# TRV-Controller.net
KiCad netlist of a schematic drawn in EasyEDA Pro
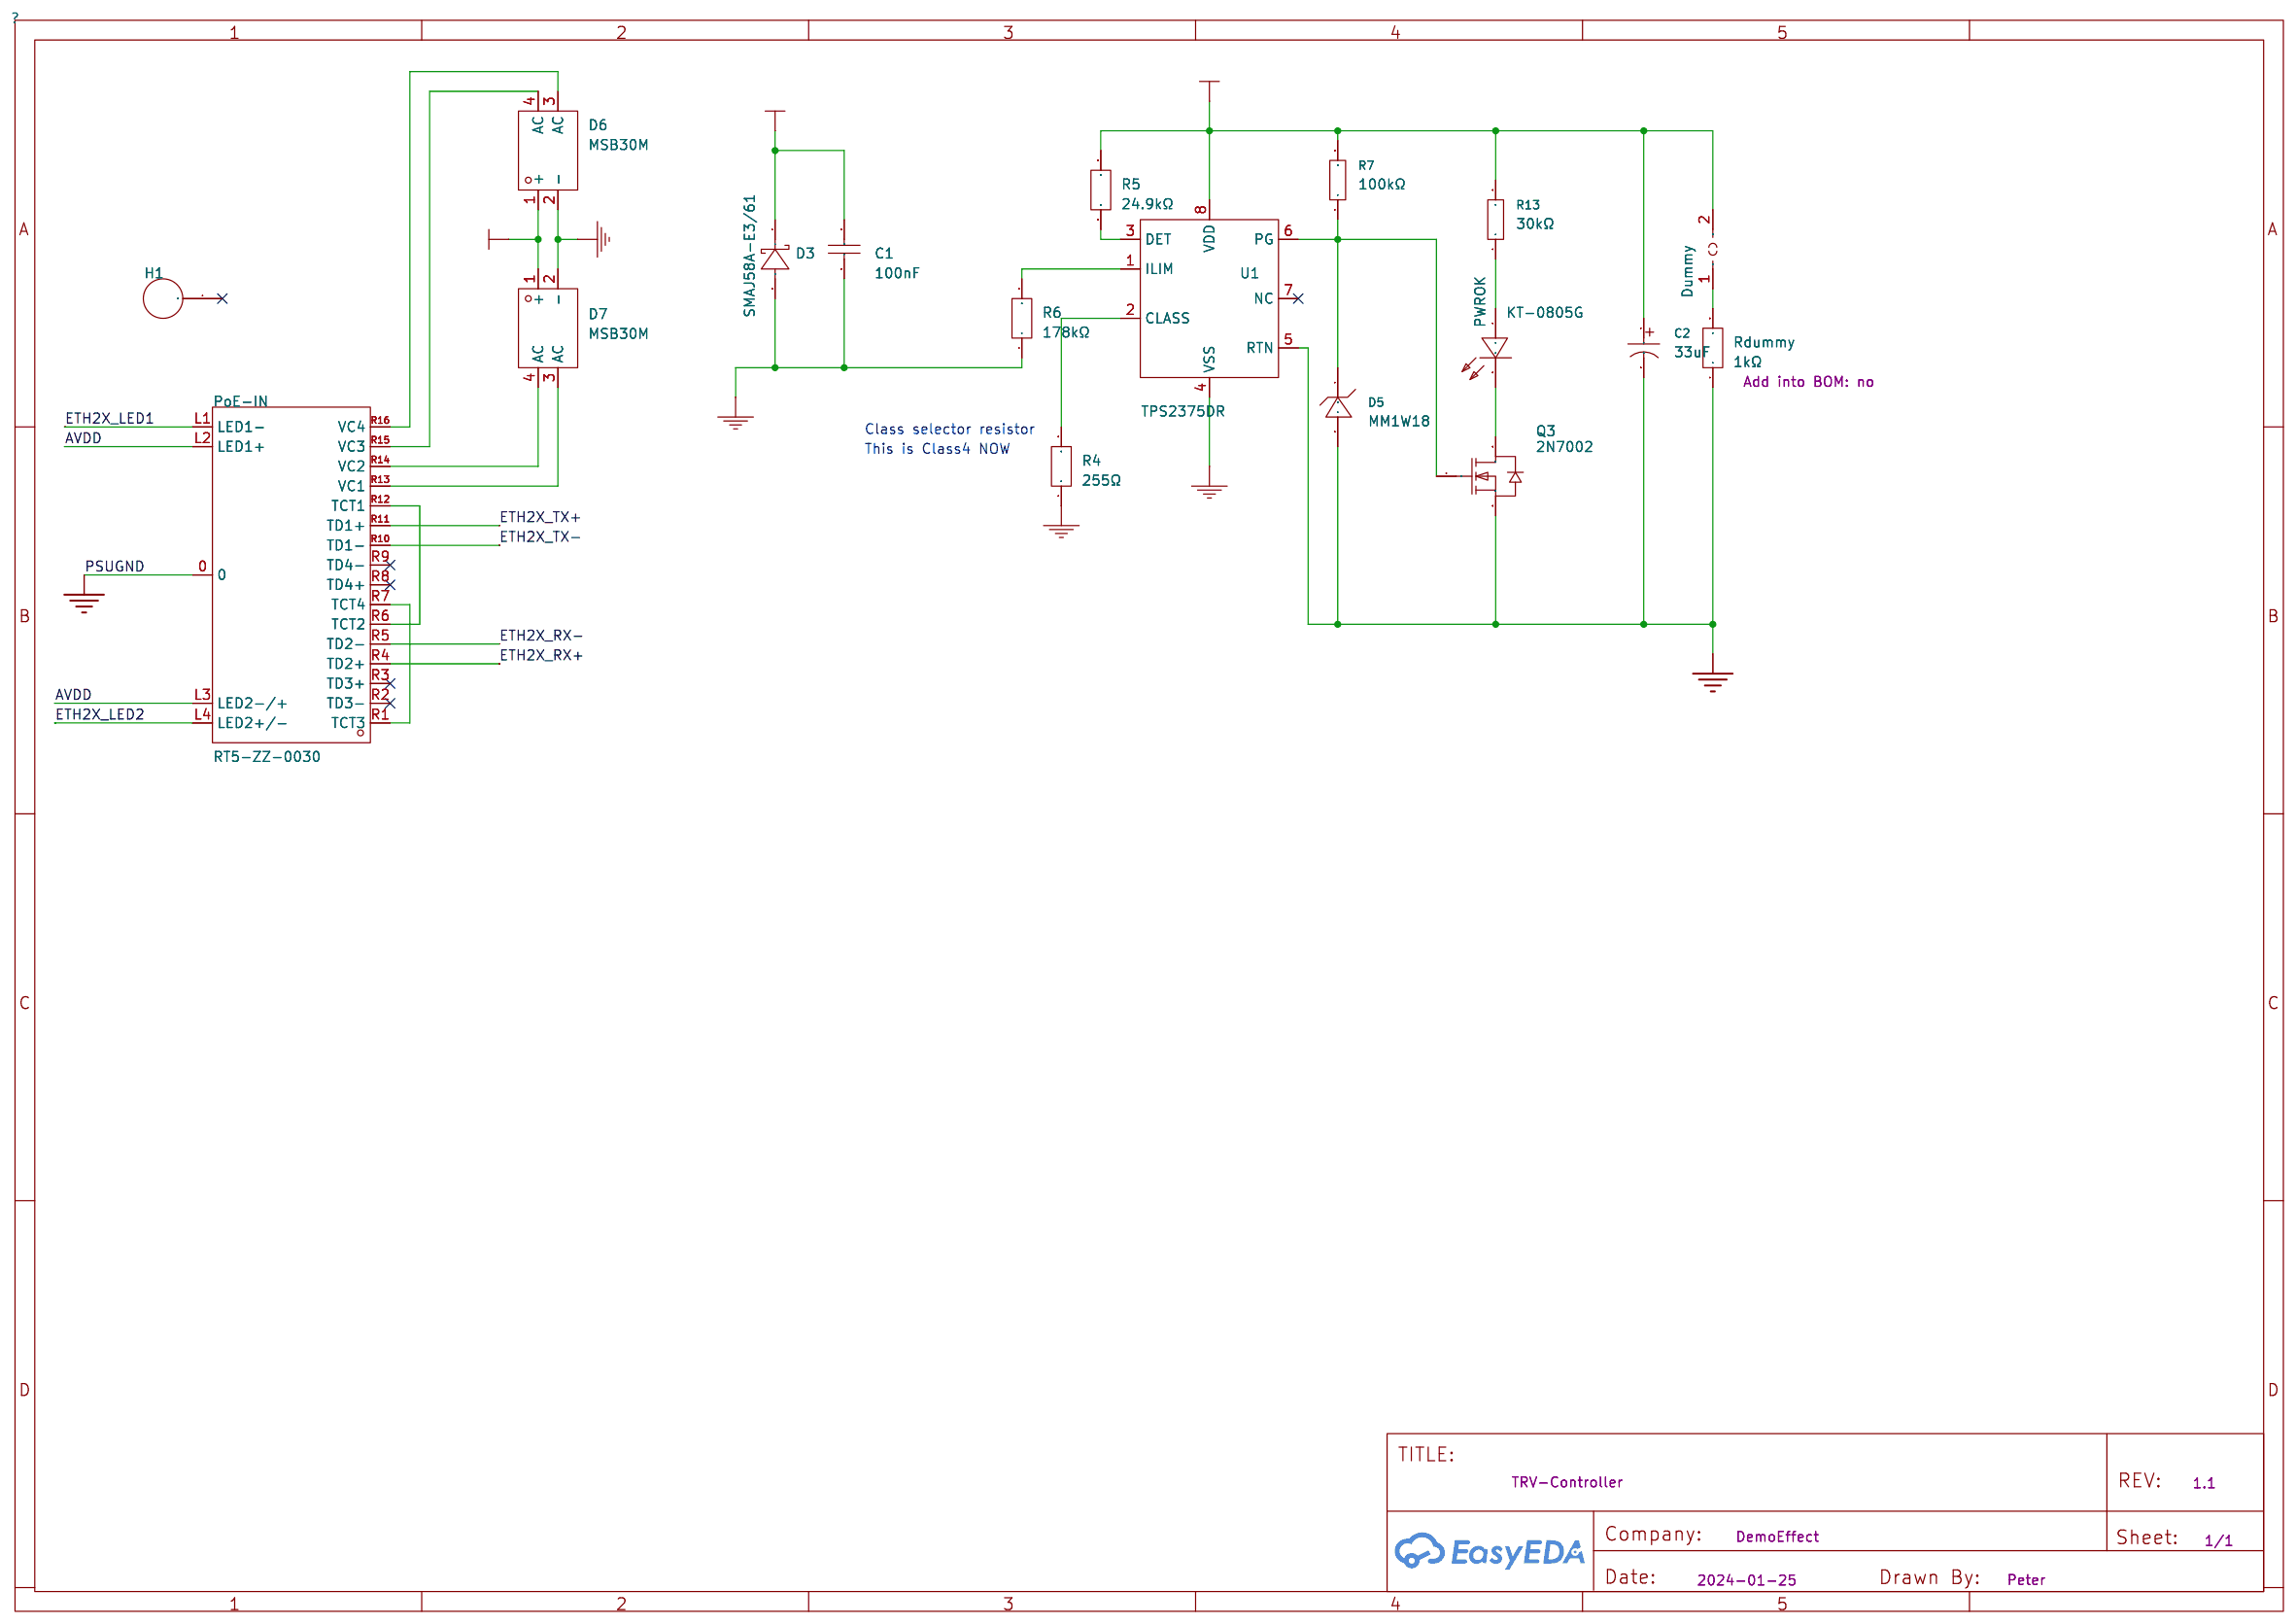
[diagram p0: PoE isolator]
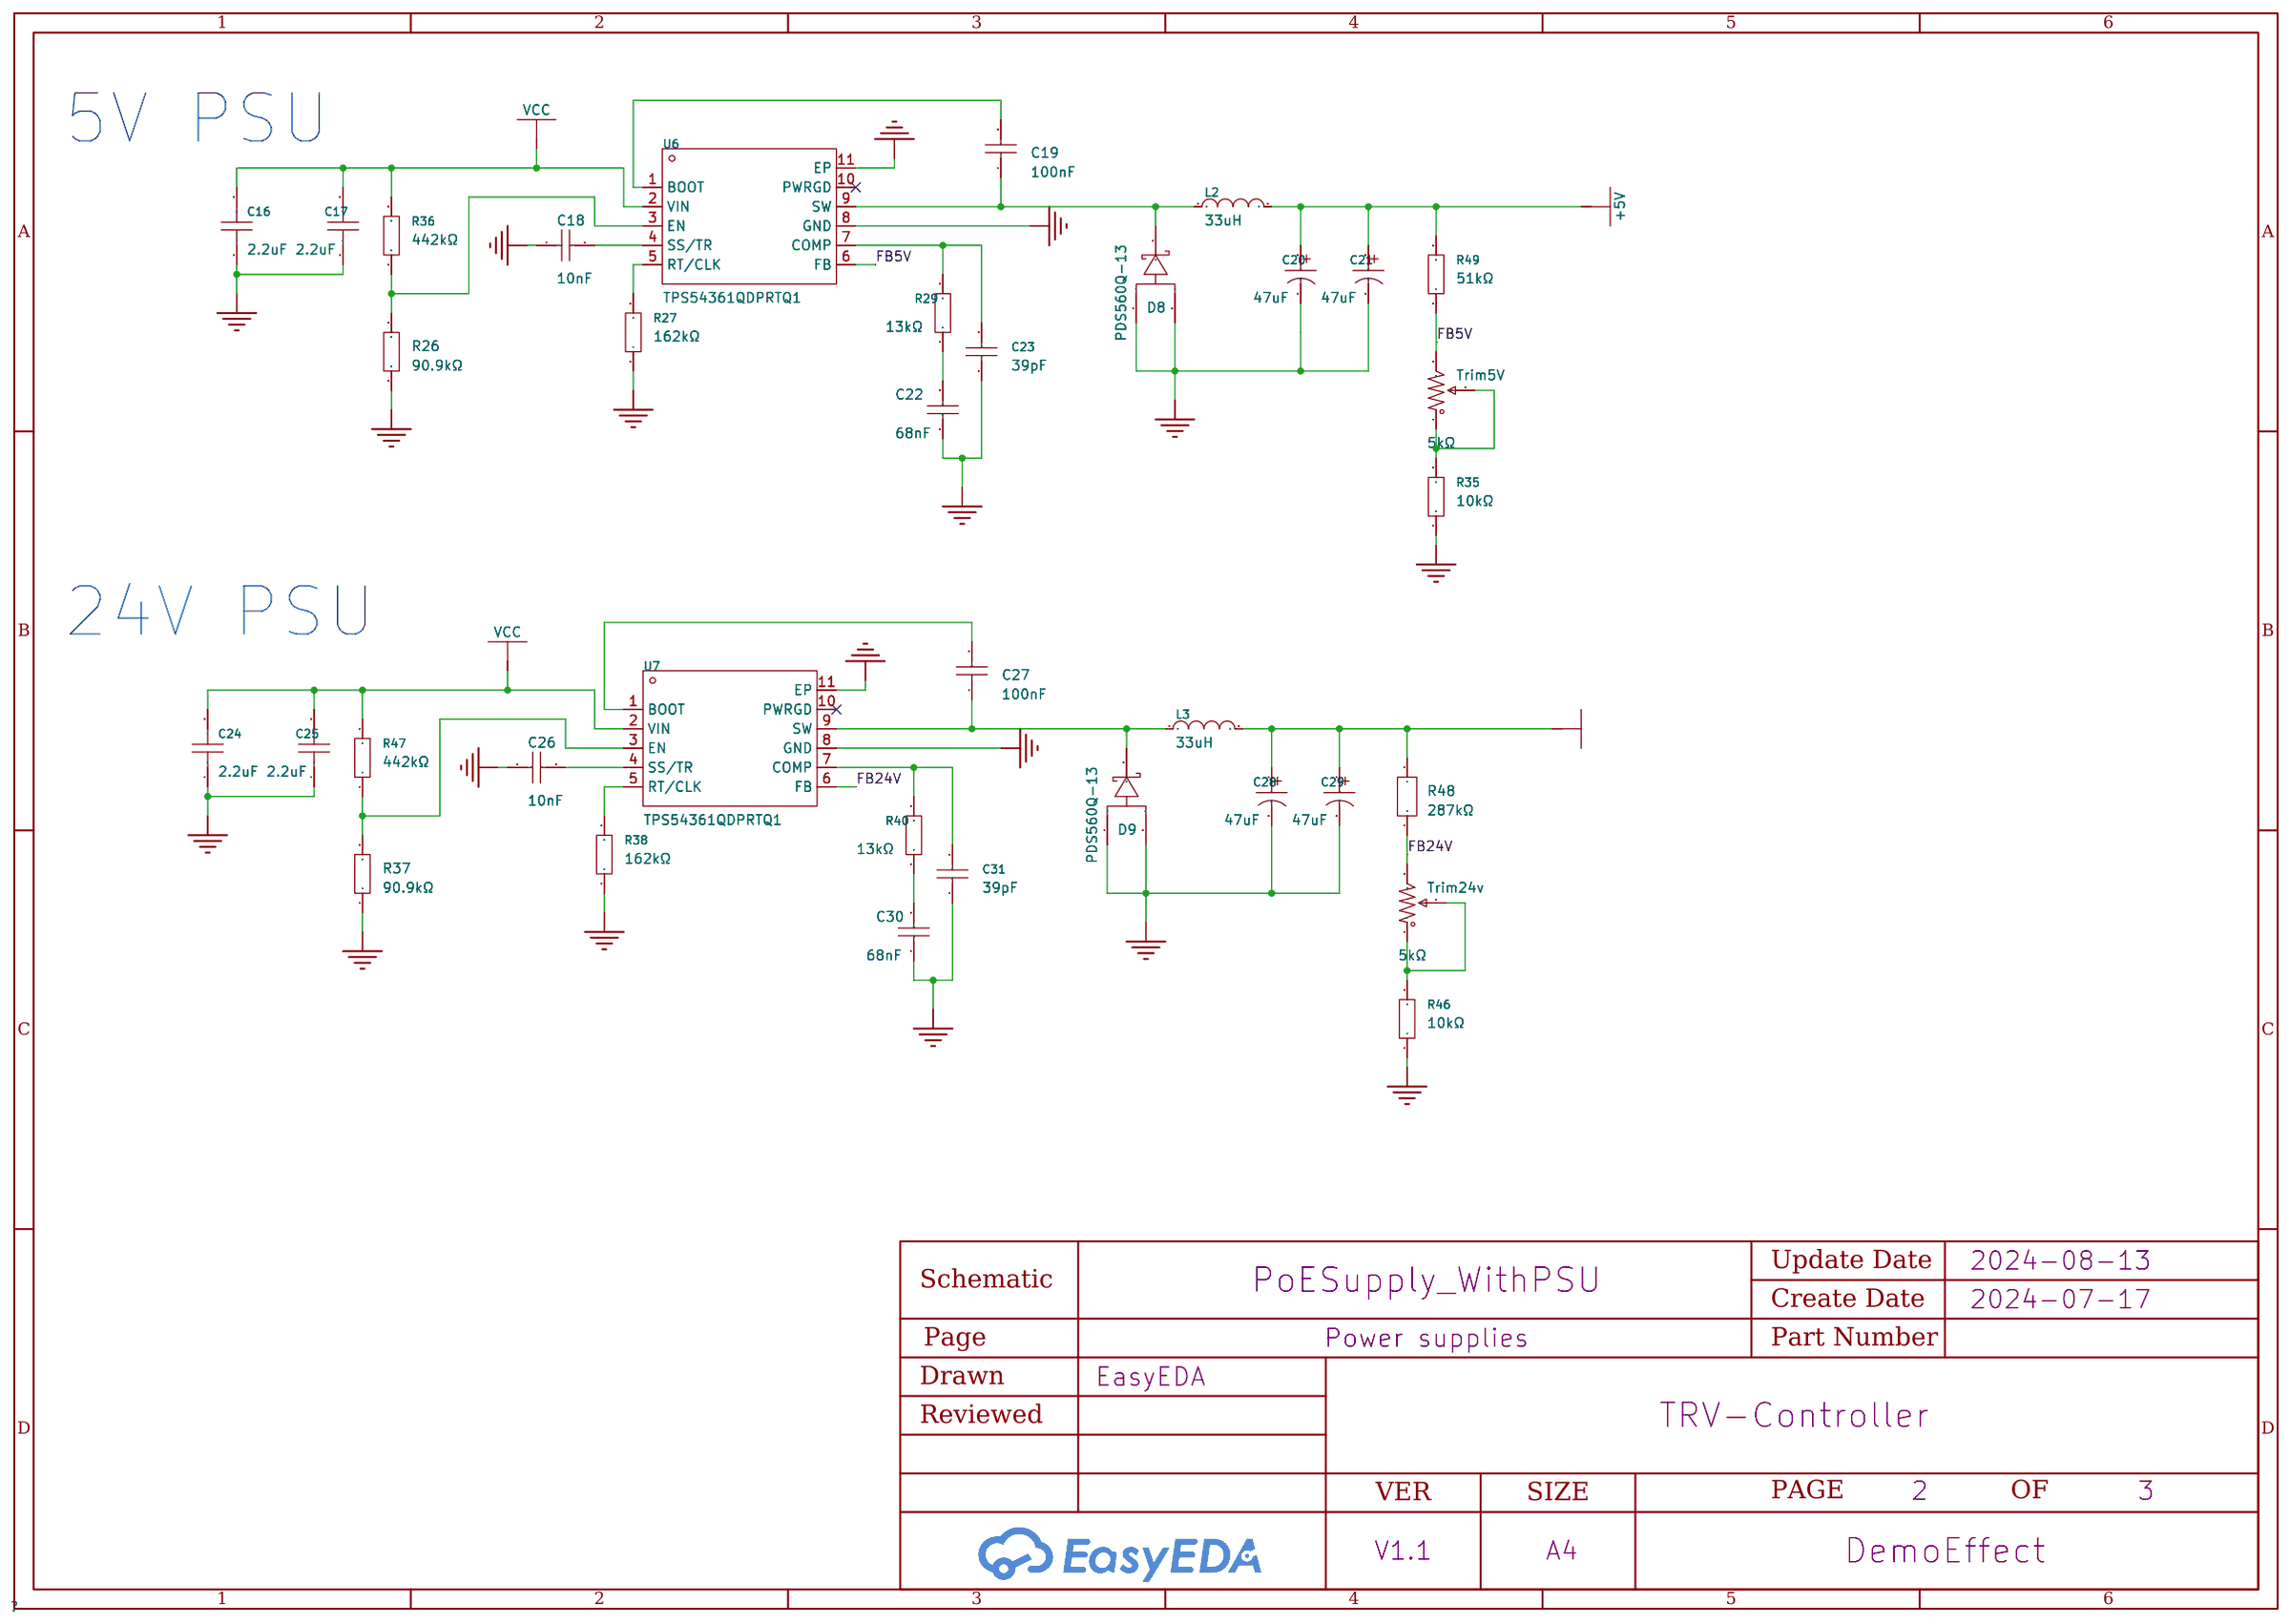
[diagram p1: Power supplies]
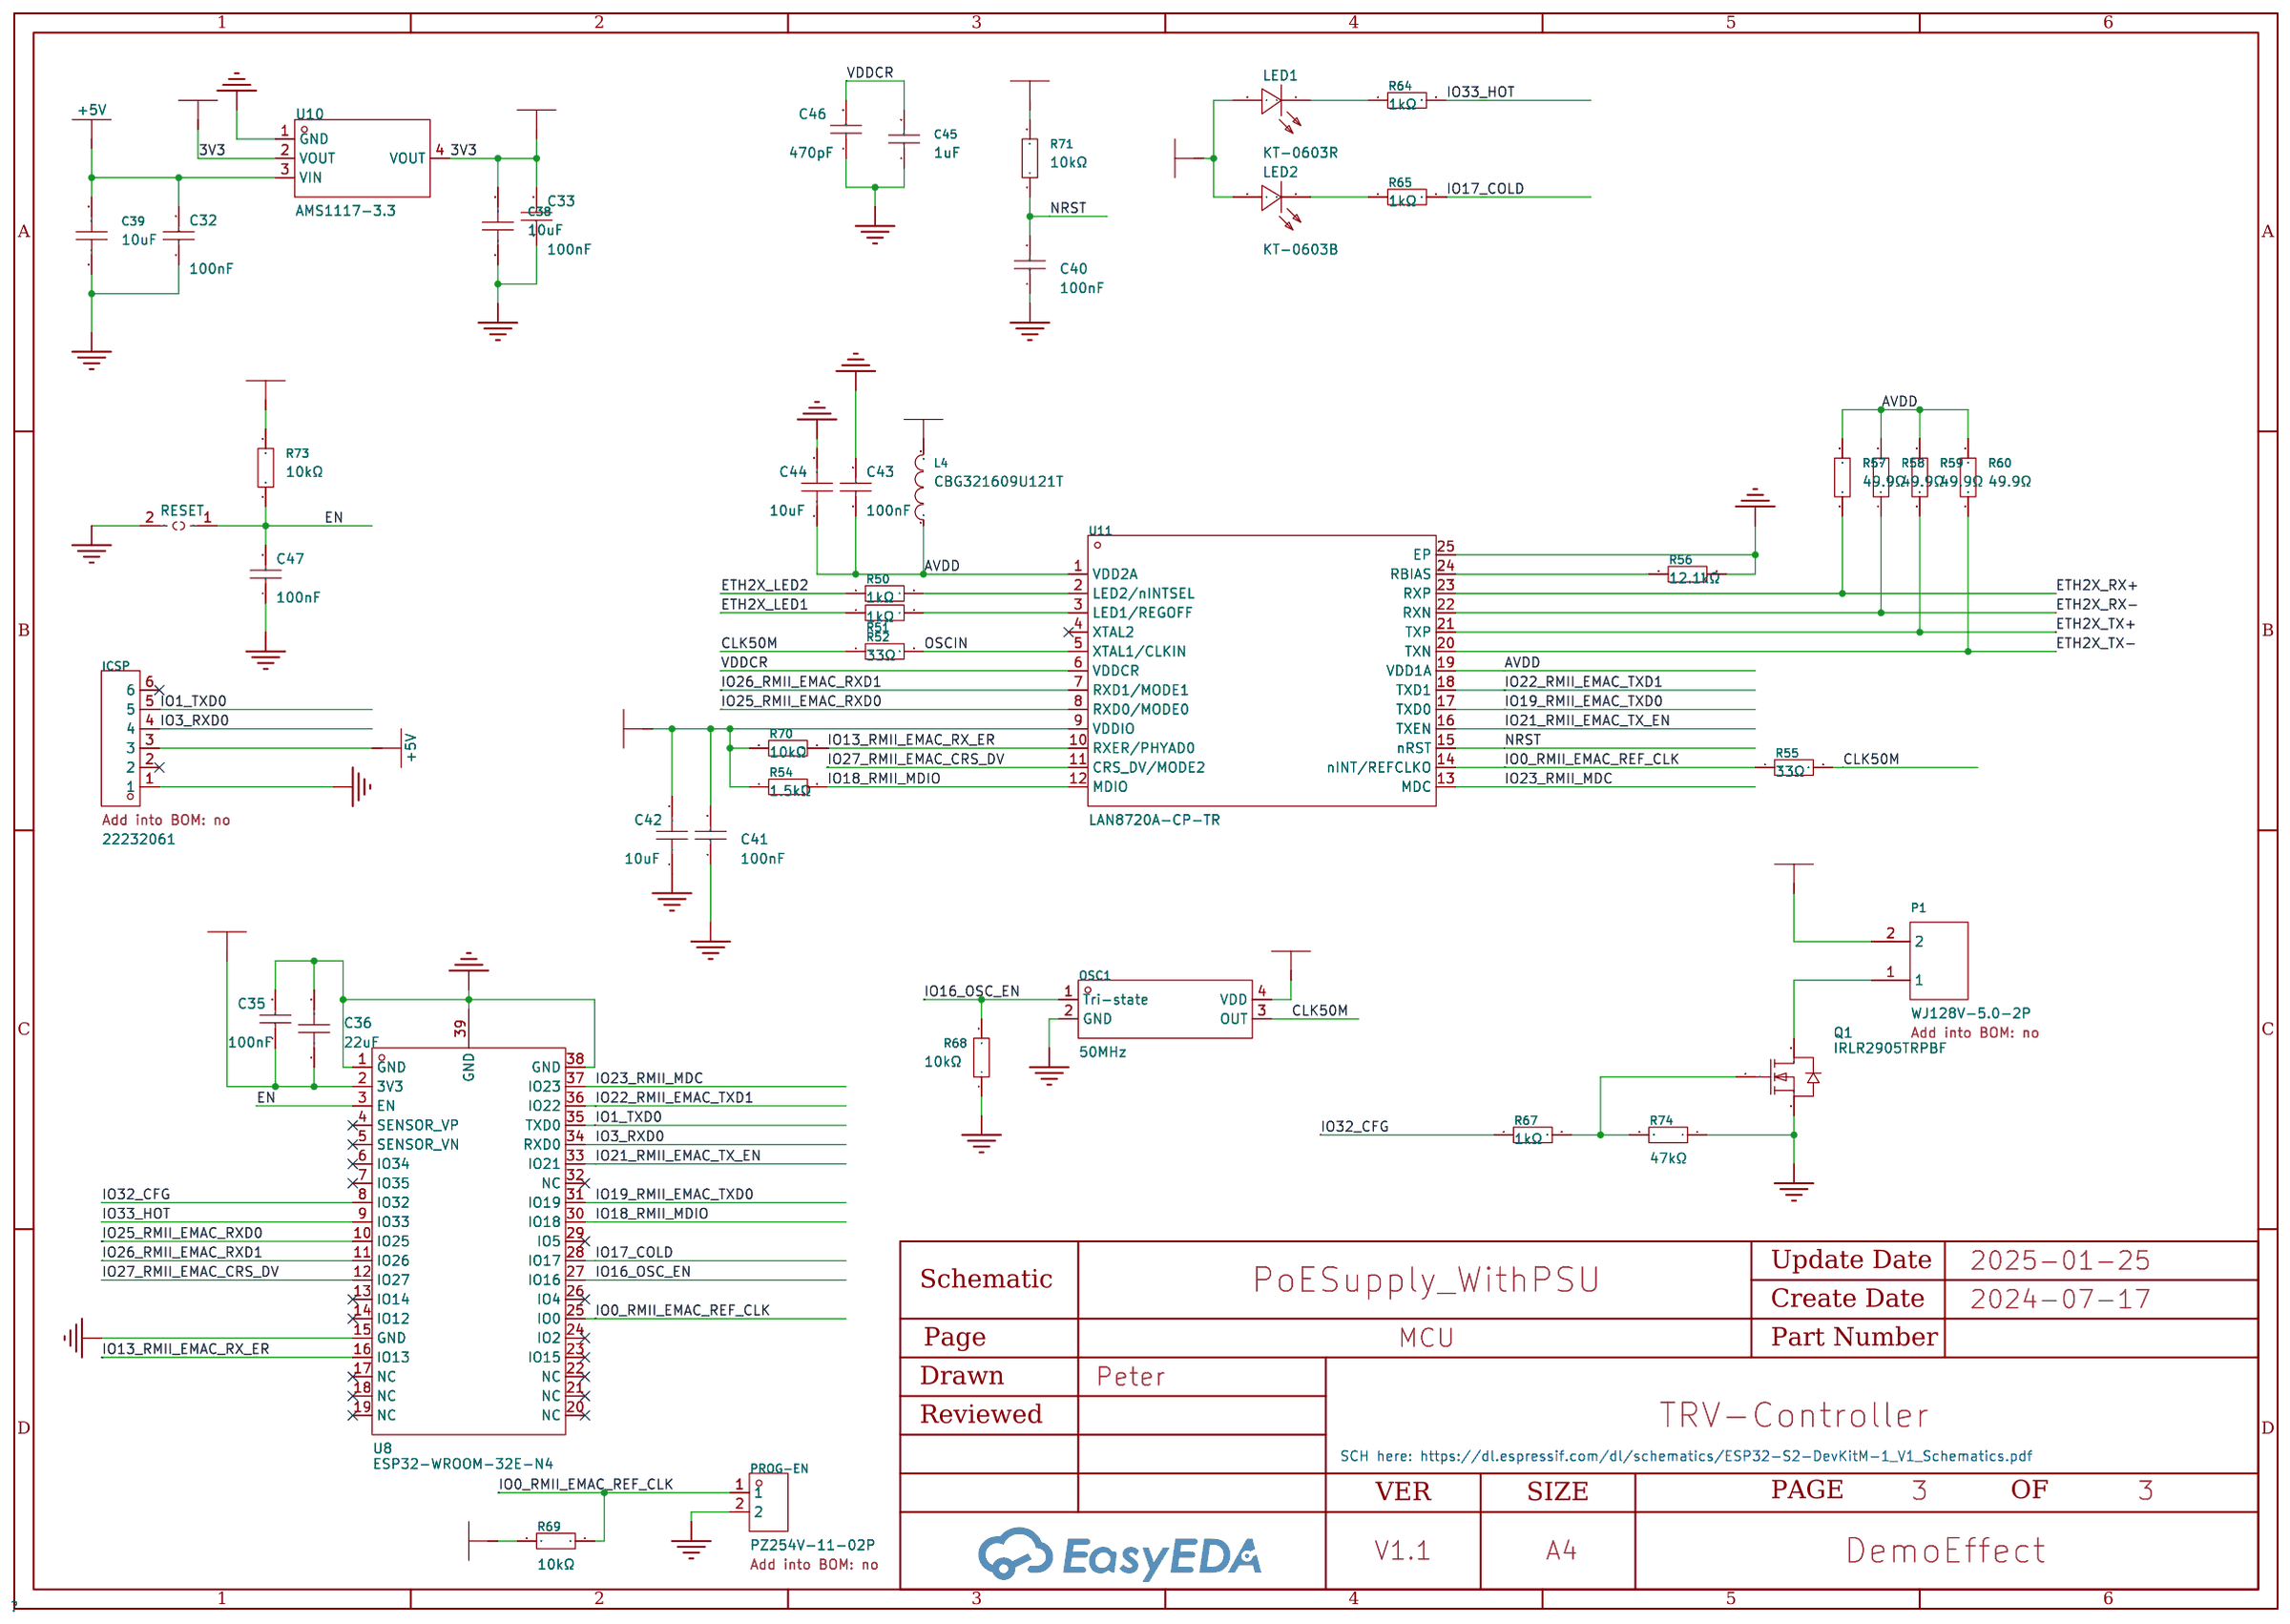
[diagram p2: MCU]

(export (version "E")
  (design (tool "Eeschema 10.0.6"))
  (components
    (comp (ref "C1")
      (value "100nF")
      (footprint "easyedapro:C0805")
      (fields
        (field (name "Manufacturer Part") "CL21B104KCFNNNE")
        (field (name "Manufacturer") "SAMSUNG(三星)")
      )
      (libsource (lib "easyedapro") (part "CL21B104KCFNNNE"))
    )
    (comp (ref "C2")
      (value "33uF")
      (footprint "easyedapro:CAP-SMD_BD10.0-L10.3-W10.3-LS11.3-FD")
      (fields (field (name "Manufacturer Part") "RVT2A330M1010") (field (name "Manufacturer") "HONOR(荣誉)"))
      (libsource (lib "easyedapro") (part "RVT2A330M1010"))
    )
    (comp (ref "D3")
      (value "SMAJ58A-E3/61")
      (footprint "easyedapro:SMA_L4.3-W2.6-LS5.1-RD")
      (fields (field (name "Manufacturer") "VISHAY(威世)"))
      (libsource (lib "easyedapro") (part "SMAJ58A-E3/61"))
    )
    (comp (ref "D5")
      (value "MM1W18")
      (footprint "easyedapro:SOD-123_L2.7-W1.6-LS3.7-RD")
      (fields (field (name "Manufacturer") "晶导微电子"))
      (libsource (lib "easyedapro") (part "MM1W18"))
    )
    (comp (ref "D6")
      (value "MSB30M")
      (footprint "easyedapro:DIO-BG-SMD_UMSB")
      (fields (field (name "Manufacturer") "MDD"))
      (libsource (lib "easyedapro") (part "MSB30M"))
    )
    (comp (ref "D7")
      (value "MSB30M")
      (footprint "easyedapro:DIO-BG-SMD_UMSB")
      (fields (field (name "Manufacturer") "MDD"))
      (libsource (lib "easyedapro") (part "MSB30M"))
    )
    (comp (ref "Dummy")
      (value "~")
      (footprint "easyedapro:SOLDERJUMPER_REFLOW_NOPASTE")
      (libsource (lib "easyedapro") (part "Solder Jumper"))
    )
    (comp (ref "H1")
      (value "~")
      (footprint "easyedapro:HOLE_D3M5_D7M0_PAD_PTH")
      (libsource (lib "easyedapro") (part "HOLE_D3M5_D7M0_PAD_PTH"))
    )
    (comp (ref "PoE-IN")
      (value "RT5-ZZ-0030")
      (footprint "easyedapro:RJ45-TH_RT5-ZZ-0030")
      (description "Connector Type:RJReceptacle USOC Codes:RJ45 Number of Ports:1")
      (fields (field (name "Manufacturer") "UDE(涌德电子)"))
      (libsource (lib "easyedapro") (part "RT5-ZZ-0030"))
    )
    (comp (ref "PWROK")
      (value "KT-0805G")
      (footprint "easyedapro:LED0805-R-RD")
      (fields (field (name "Manufacturer") "KENTO"))
      (libsource (lib "easyedapro") (part "0805G (Green)"))
    )
    (comp (ref "Q3")
      (value "2N7002")
      (footprint "easyedapro:SOT-23-3_L2.9-W1.3-P1.90-LS2.4-BR")
      (fields (field (name "Manufacturer") "CJ(江苏长电/长晶)"))
      (libsource (lib "easyedapro") (part "2N7002"))
    )
    (comp (ref "R4")
      (value "255Ω")
      (footprint "easyedapro:R1210")
      (fields (field (name "Manufacturer Part") "AC1210FR-07255RL") (field (name "Manufacturer") "YAGEO(国巨)"))
      (libsource (lib "easyedapro") (part "AC1210FR-07255RL"))
    )
    (comp (ref "R5")
      (value "24.9kΩ")
      (footprint "easyedapro:R1210")
      (fields (field (name "Manufacturer Part") "AC1210FR-0724K9L") (field (name "Manufacturer") "YAGEO(国巨)"))
      (libsource (lib "easyedapro") (part "AC1210FR-0724K9L"))
    )
    (comp (ref "R6")
      (value "178kΩ")
      (footprint "easyedapro:R1210")
      (fields (field (name "Manufacturer Part") "AC1210FR-07178KL") (field (name "Manufacturer") "YAGEO(国巨)"))
      (libsource (lib "easyedapro") (part "AC1210FR-07178KL"))
    )
    (comp (ref "R7")
      (value "100kΩ")
      (footprint "easyedapro:R1206")
      (fields
        (field (name "Manufacturer Part") "1206W4F1003T5E")
        (field (name "Manufacturer") "UNI-ROYAL(厚声)")
      )
      (libsource (lib "easyedapro") (part "1206W4F1003T5E"))
    )
    (comp (ref "R13")
      (value "30kΩ")
      (footprint "easyedapro:R0603")
      (fields
        (field (name "Manufacturer Part") "0603WAF3002T5E")
        (field (name "Manufacturer") "UNI-ROYAL(厚声)")
      )
      (libsource (lib "easyedapro") (part "0603WAF3002T5E"))
    )
    (comp (ref "Rdummy")
      (value "1kΩ")
      (footprint "easyedapro:RES-TH_BD2.3-L6.5-P10.50-D0.5")
      (fields
        (field (name "Manufacturer Part") "MF1/4W-1KΩ±1%T52")
        (field (name "Manufacturer") "华星机电")
        (field (name "Add into BOM") "no")
      )
      (libsource (lib "easyedapro") (part "MF1/4W-1KΩ±1%T52"))
    )
    (comp (ref "U1")
      (value "TPS2375DR")
      (footprint "easyedapro:SOIC-8_L4.9-W3.9-P1.27-LS6.0-BL")
      (fields (field (name "Manufacturer") "TI(德州仪器)"))
      (libsource (lib "easyedapro") (part "TPS2375DR"))
    )
    (comp (ref "C16")
      (value "2.2uF")
      (footprint "easyedapro:C1210")
      (fields
        (field (name "Manufacturer Part") "GRM32ER72A225KA35L")
        (field (name "Manufacturer") "muRata(村田)")
      )
      (libsource (lib "easyedapro") (part "GRM32ER72A225KA35L"))
    )
    (comp (ref "C17")
      (value "2.2uF")
      (footprint "easyedapro:C1210")
      (fields
        (field (name "Manufacturer Part") "GRM32ER72A225KA35L")
        (field (name "Manufacturer") "muRata(村田)")
      )
      (libsource (lib "easyedapro") (part "GRM32ER72A225KA35L"))
    )
    (comp (ref "C18")
      (value "10nF")
      (footprint "easyedapro:C0805")
      (fields
        (field (name "Manufacturer Part") "CL21B103KBANNNC")
        (field (name "Manufacturer") "SAMSUNG(三星)")
      )
      (libsource (lib "easyedapro") (part "CL21B103KBANNNC"))
    )
    (comp (ref "C19")
      (value "100nF")
      (footprint "easyedapro:C0805")
      (fields
        (field (name "Manufacturer Part") "CL21B104KCFNNNE")
        (field (name "Manufacturer") "SAMSUNG(三星)")
      )
      (libsource (lib "easyedapro") (part "CL21B104KCFNNNE"))
    )
    (comp (ref "C20")
      (value "47uF")
      (footprint "easyedapro:CAP-SMD_BD6.3-L6.6-W6.6-LS7.6-FD")
      (fields (field (name "Manufacturer Part") "RVT1H470M0607") (field (name "Manufacturer") "ROQANG(容强)"))
      (libsource (lib "easyedapro") (part "RVT1H470M0607"))
    )
    (comp (ref "C21")
      (value "47uF")
      (footprint "easyedapro:CAP-SMD_BD6.3-L6.6-W6.6-LS7.6-FD")
      (fields (field (name "Manufacturer Part") "RVT1H470M0607") (field (name "Manufacturer") "ROQANG(容强)"))
      (libsource (lib "easyedapro") (part "RVT1H470M0607"))
    )
    (comp (ref "C22")
      (value "68nF")
      (footprint "easyedapro:C0603")
      (fields
        (field (name "Manufacturer Part") "CL10B683KB8NNNC")
        (field (name "Manufacturer") "SAMSUNG(三星)")
      )
      (libsource (lib "easyedapro") (part "CL10B683KB8NNNC"))
    )
    (comp (ref "C23")
      (value "39pF")
      (footprint "easyedapro:C0603")
      (fields
        (field (name "Manufacturer Part") "CC0603JRNPO9BN390")
        (field (name "Manufacturer") "YAGEO(国巨)")
      )
      (libsource (lib "easyedapro") (part "CC0603JRNPO9BN390"))
    )
    (comp (ref "C24")
      (value "2.2uF")
      (footprint "easyedapro:C1210")
      (fields
        (field (name "Manufacturer Part") "GRM32ER72A225KA35L")
        (field (name "Manufacturer") "muRata(村田)")
      )
      (libsource (lib "easyedapro") (part "GRM32ER72A225KA35L"))
    )
    (comp (ref "C25")
      (value "2.2uF")
      (footprint "easyedapro:C1210")
      (fields
        (field (name "Manufacturer Part") "GRM32ER72A225KA35L")
        (field (name "Manufacturer") "muRata(村田)")
      )
      (libsource (lib "easyedapro") (part "GRM32ER72A225KA35L"))
    )
    (comp (ref "C26")
      (value "10nF")
      (footprint "easyedapro:C0805")
      (fields
        (field (name "Manufacturer Part") "CL21B103KBANNNC")
        (field (name "Manufacturer") "SAMSUNG(三星)")
      )
      (libsource (lib "easyedapro") (part "CL21B103KBANNNC"))
    )
    (comp (ref "C27")
      (value "100nF")
      (footprint "easyedapro:C0805")
      (fields
        (field (name "Manufacturer Part") "CL21B104KCFNNNE")
        (field (name "Manufacturer") "SAMSUNG(三星)")
      )
      (libsource (lib "easyedapro") (part "CL21B104KCFNNNE"))
    )
    (comp (ref "C28")
      (value "47uF")
      (footprint "easyedapro:CAP-SMD_BD6.3-L6.6-W6.6-LS7.6-FD")
      (fields (field (name "Manufacturer Part") "RVT1H470M0607") (field (name "Manufacturer") "ROQANG(容强)"))
      (libsource (lib "easyedapro") (part "RVT1H470M0607"))
    )
    (comp (ref "C29")
      (value "47uF")
      (footprint "easyedapro:CAP-SMD_BD6.3-L6.6-W6.6-LS7.6-FD")
      (fields (field (name "Manufacturer Part") "RVT1H470M0607") (field (name "Manufacturer") "ROQANG(容强)"))
      (libsource (lib "easyedapro") (part "RVT1H470M0607"))
    )
    (comp (ref "C30")
      (value "68nF")
      (footprint "easyedapro:C0603")
      (fields
        (field (name "Manufacturer Part") "CL10B683KB8NNNC")
        (field (name "Manufacturer") "SAMSUNG(三星)")
      )
      (libsource (lib "easyedapro") (part "CL10B683KB8NNNC"))
    )
    (comp (ref "C31")
      (value "39pF")
      (footprint "easyedapro:C0603")
      (fields
        (field (name "Manufacturer Part") "CC0603JRNPO9BN390")
        (field (name "Manufacturer") "YAGEO(国巨)")
      )
      (libsource (lib "easyedapro") (part "CC0603JRNPO9BN390"))
    )
    (comp (ref "D8")
      (value "PDS560Q-13")
      (footprint "easyedapro:POWERDI-5_L5.4-W4.0-LS6.5-RD")
      (fields (field (name "Manufacturer") "DIODES(美台)"))
      (libsource (lib "easyedapro") (part "PDS560Q-13"))
    )
    (comp (ref "D9")
      (value "PDS560Q-13")
      (footprint "easyedapro:POWERDI-5_L5.4-W4.0-LS6.5-RD")
      (fields (field (name "Manufacturer") "DIODES(美台)"))
      (libsource (lib "easyedapro") (part "PDS560Q-13"))
    )
    (comp (ref "L2")
      (value "33uH")
      (footprint "easyedapro:IND-SMD_L11.5-W10.0_FXL1040")
      (fields (field (name "Manufacturer Part") "FXL1040-330-M") (field (name "Manufacturer") "cjiang(长江微电)"))
      (libsource (lib "easyedapro") (part "FXL1040-330-M"))
    )
    (comp (ref "L3")
      (value "33uH")
      (footprint "easyedapro:IND-SMD_L11.5-W10.0_FXL1040")
      (fields (field (name "Manufacturer Part") "FXL1040-330-M") (field (name "Manufacturer") "cjiang(长江微电)"))
      (libsource (lib "easyedapro") (part "FXL1040-330-M"))
    )
    (comp (ref "R26")
      (value "90.9kΩ")
      (footprint "easyedapro:R0402")
      (fields (field (name "Manufacturer Part") "RC0402FR-0790K9L") (field (name "Manufacturer") "YAGEO(国巨)"))
      (libsource (lib "easyedapro") (part "RC0402FR-0790K9L"))
    )
    (comp (ref "R27")
      (value "162kΩ")
      (footprint "easyedapro:R0603")
      (fields
        (field (name "Manufacturer Part") "0603WAF1623T5E")
        (field (name "Manufacturer") "UNI-ROYAL(厚声)")
      )
      (libsource (lib "easyedapro") (part "0603WAF1623T5E"))
    )
    (comp (ref "R29")
      (value "13kΩ")
      (footprint "easyedapro:R0603")
      (fields
        (field (name "Manufacturer Part") "0603WAF1302T5E")
        (field (name "Manufacturer") "UNI-ROYAL(厚声)")
      )
      (libsource (lib "easyedapro") (part "0603WAF1302T5E"))
    )
    (comp (ref "R35")
      (value "10kΩ")
      (footprint "easyedapro:R0603")
      (fields
        (field (name "Manufacturer Part") "0603WAF1002T5E")
        (field (name "Manufacturer") "UNI-ROYAL(厚声)")
      )
      (libsource (lib "easyedapro") (part "0603WAF1002T5E"))
    )
    (comp (ref "R36")
      (value "442kΩ")
      (footprint "easyedapro:R0402")
      (fields
        (field (name "Manufacturer Part") "0402WGF4423TCE")
        (field (name "Manufacturer") "UNI-ROYAL(厚声)")
      )
      (libsource (lib "easyedapro") (part "0402WGF4423TCE"))
    )
    (comp (ref "R37")
      (value "90.9kΩ")
      (footprint "easyedapro:R0402")
      (fields (field (name "Manufacturer Part") "RC0402FR-0790K9L") (field (name "Manufacturer") "YAGEO(国巨)"))
      (libsource (lib "easyedapro") (part "RC0402FR-0790K9L"))
    )
    (comp (ref "R38")
      (value "162kΩ")
      (footprint "easyedapro:R0603")
      (fields
        (field (name "Manufacturer Part") "0603WAF1623T5E")
        (field (name "Manufacturer") "UNI-ROYAL(厚声)")
      )
      (libsource (lib "easyedapro") (part "0603WAF1623T5E"))
    )
    (comp (ref "R40")
      (value "13kΩ")
      (footprint "easyedapro:R0603")
      (fields
        (field (name "Manufacturer Part") "0603WAF1302T5E")
        (field (name "Manufacturer") "UNI-ROYAL(厚声)")
      )
      (libsource (lib "easyedapro") (part "0603WAF1302T5E"))
    )
    (comp (ref "R46")
      (value "10kΩ")
      (footprint "easyedapro:R0603")
      (fields
        (field (name "Manufacturer Part") "0603WAF1002T5E")
        (field (name "Manufacturer") "UNI-ROYAL(厚声)")
      )
      (libsource (lib "easyedapro") (part "0603WAF1002T5E"))
    )
    (comp (ref "R47")
      (value "442kΩ")
      (footprint "easyedapro:R0402")
      (fields
        (field (name "Manufacturer Part") "0402WGF4423TCE")
        (field (name "Manufacturer") "UNI-ROYAL(厚声)")
      )
      (libsource (lib "easyedapro") (part "0402WGF4423TCE"))
    )
    (comp (ref "R48")
      (value "287kΩ")
      (footprint "easyedapro:R0805")
      (fields (field (name "Manufacturer Part") "FRC0805F2873TS") (field (name "Manufacturer") "FOJAN(富捷)"))
      (libsource (lib "easyedapro") (part "FRC0805F2873TS"))
    )
    (comp (ref "R49")
      (value "51kΩ")
      (footprint "easyedapro:R0402")
      (fields
        (field (name "Manufacturer Part") "0402WGF5102TCE")
        (field (name "Manufacturer") "UNI-ROYAL(厚声)")
      )
      (libsource (lib "easyedapro") (part "0402WGF5102TCE"))
    )
    (comp (ref "Trim5V")
      (value "5kΩ")
      (footprint "easyedapro:RES-ADJ-SMD_3P-L4.5-W4.5-P2.35-BR")
      (fields (field (name "Manufacturer Part") "3314G-1-502E") (field (name "Manufacturer") "BOURNS"))
      (libsource (lib "easyedapro") (part "3314G-1-502E"))
    )
    (comp (ref "Trim24v")
      (value "5kΩ")
      (footprint "easyedapro:RES-ADJ-SMD_3P-L4.5-W4.5-P2.35-BR")
      (fields (field (name "Manufacturer Part") "3314G-1-502E") (field (name "Manufacturer") "BOURNS"))
      (libsource (lib "easyedapro") (part "3314G-1-502E"))
    )
    (comp (ref "U6")
      (value "TPS54361QDPRTQ1")
      (footprint "easyedapro:WSON-10_L4.0-W4.0-P0.80-TL-EP")
      (fields (field (name "Manufacturer") "TI(德州仪器)"))
      (libsource (lib "easyedapro") (part "TPS54361QDPRTQ1"))
    )
    (comp (ref "U7")
      (value "TPS54361QDPRTQ1")
      (footprint "easyedapro:WSON-10_L4.0-W4.0-P0.80-TL-EP")
      (fields (field (name "Manufacturer") "TI(德州仪器)"))
      (libsource (lib "easyedapro") (part "TPS54361QDPRTQ1"))
    )
    (comp (ref "C32")
      (value "100nF")
      (footprint "easyedapro:C0805")
      (fields
        (field (name "Manufacturer Part") "CL21B104KCFNNNE")
        (field (name "Manufacturer") "SAMSUNG(三星)")
      )
      (libsource (lib "easyedapro") (part "CL21B104KCFNNNE"))
    )
    (comp (ref "C33")
      (value "100nF")
      (footprint "easyedapro:C0805")
      (fields
        (field (name "Manufacturer Part") "CL21B104KCFNNNE")
        (field (name "Manufacturer") "SAMSUNG(三星)")
      )
      (libsource (lib "easyedapro") (part "CL21B104KCFNNNE"))
    )
    (comp (ref "C35")
      (value "100nF")
      (footprint "easyedapro:C0805")
      (fields
        (field (name "Manufacturer Part") "CL21B104KCFNNNE")
        (field (name "Manufacturer") "SAMSUNG(三星)")
      )
      (libsource (lib "easyedapro") (part "CL21B104KCFNNNE"))
    )
    (comp (ref "C36")
      (value "22uF")
      (footprint "easyedapro:C0805")
      (fields
        (field (name "Manufacturer Part") "CL21A226MAQNNNE")
        (field (name "Manufacturer") "SAMSUNG(三星)")
      )
      (libsource (lib "easyedapro") (part "CL21A226MAQNNNE"))
    )
    (comp (ref "C38")
      (value "10uF")
      (footprint "easyedapro:C0603")
      (fields
        (field (name "Manufacturer Part") "CL10A106KP8NNNC")
        (field (name "Manufacturer") "SAMSUNG(三星)")
      )
      (libsource (lib "easyedapro") (part "CL10A106KP8NNNC"))
    )
    (comp (ref "C39")
      (value "10uF")
      (footprint "easyedapro:C0603")
      (fields
        (field (name "Manufacturer Part") "CL10A106KP8NNNC")
        (field (name "Manufacturer") "SAMSUNG(三星)")
      )
      (libsource (lib "easyedapro") (part "CL10A106KP8NNNC"))
    )
    (comp (ref "C40")
      (value "100nF")
      (footprint "easyedapro:C0805")
      (fields
        (field (name "Manufacturer Part") "CL21B104KCFNNNE")
        (field (name "Manufacturer") "SAMSUNG(三星)")
      )
      (libsource (lib "easyedapro") (part "CL21B104KCFNNNE"))
    )
    (comp (ref "C41")
      (value "100nF")
      (footprint "easyedapro:C0805")
      (fields
        (field (name "Manufacturer Part") "CL21B104KCFNNNE")
        (field (name "Manufacturer") "SAMSUNG(三星)")
      )
      (libsource (lib "easyedapro") (part "CL21B104KCFNNNE"))
    )
    (comp (ref "C42")
      (value "10uF")
      (footprint "easyedapro:C0805")
      (fields
        (field (name "Manufacturer Part") "CL21A106KAYNNNE")
        (field (name "Manufacturer") "SAMSUNG(三星)")
      )
      (libsource (lib "easyedapro") (part "CL21A106KAYNNNE"))
    )
    (comp (ref "C43")
      (value "100nF")
      (footprint "easyedapro:C0805")
      (fields
        (field (name "Manufacturer Part") "CL21B104KCFNNNE")
        (field (name "Manufacturer") "SAMSUNG(三星)")
      )
      (libsource (lib "easyedapro") (part "CL21B104KCFNNNE"))
    )
    (comp (ref "C44")
      (value "10uF")
      (footprint "easyedapro:C0805")
      (fields
        (field (name "Manufacturer Part") "CL21A106KAYNNNE")
        (field (name "Manufacturer") "SAMSUNG(三星)")
      )
      (libsource (lib "easyedapro") (part "CL21A106KAYNNNE"))
    )
    (comp (ref "C45")
      (value "1uF")
      (footprint "easyedapro:C0805")
      (fields
        (field (name "Manufacturer Part") "CL21B105KBFNNNE")
        (field (name "Manufacturer") "SAMSUNG(三星)")
      )
      (libsource (lib "easyedapro") (part "CL21B105KBFNNNE"))
    )
    (comp (ref "C46")
      (value "470pF")
      (footprint "easyedapro:C0805")
      (fields (field (name "Manufacturer Part") "0805B471K500NT") (field (name "Manufacturer") "FH(风华)"))
      (libsource (lib "easyedapro") (part "0805B471K500NT"))
    )
    (comp (ref "C47")
      (value "100nF")
      (footprint "easyedapro:C0805")
      (fields
        (field (name "Manufacturer Part") "CL21B104KCFNNNE")
        (field (name "Manufacturer") "SAMSUNG(三星)")
      )
      (libsource (lib "easyedapro") (part "CL21B104KCFNNNE"))
    )
    (comp (ref "ICSP")
      (value "22232061")
      (footprint "easyedapro:CONN-TH_6P-P2.54_22232061")
      (fields (field (name "Manufacturer") "MOLEX") (field (name "Add into BOM") "no"))
      (libsource (lib "easyedapro") (part "22232061"))
    )
    (comp (ref "L4")
      (value "CBG321609U121T")
      (footprint "easyedapro:L1206")
      (fields (field (name "Manufacturer") "FH(风华)"))
      (libsource (lib "easyedapro") (part "CBG321609U121T"))
    )
    (comp (ref "LED1")
      (value "KT-0603R")
      (footprint "easyedapro:LED0603-RD")
      (fields (field (name "Manufacturer") "KENTO"))
      (libsource (lib "easyedapro") (part "KT-0603R"))
    )
    (comp (ref "LED2")
      (value "KT-0603B")
      (footprint "easyedapro:LED0603-RD")
      (fields (field (name "Manufacturer") "KENTO"))
      (libsource (lib "easyedapro") (part "Blue light 0603"))
    )
    (comp (ref "OSC1")
      (value "50MHz")
      (footprint "easyedapro:OSC-SMD_4P-L3.2-W2.5-BL")
      (fields
        (field (name "Manufacturer Part") "OT2EL4C4JI-111OLP-50M")
        (field (name "Manufacturer") "YXC(扬兴晶振)")
      )
      (libsource (lib "easyedapro") (part "OT2EL4C4JI-111OLP-50M"))
    )
    (comp (ref "P1")
      (value "WJ128V-5.0-2P")
      (footprint "easyedapro:CONN-TH_2P-P5.00_WJ128V-5.0-2P")
      (fields (field (name "Manufacturer") "KANGNEX(康奈克斯电气)") (field (name "Add into BOM") "no"))
      (libsource (lib "easyedapro") (part "WJ128V-5.0-2P"))
    )
    (comp (ref "PROG-EN")
      (value "PZ254V-11-02P")
      (footprint "easyedapro:HDR-TH_2P-P2.54-V-M")
      (fields (field (name "Manufacturer") "XFCN(兴飞)") (field (name "Add into BOM") "no"))
      (libsource (lib "easyedapro") (part "PZ254V-11-02P"))
    )
    (comp (ref "Q1")
      (value "IRLR2905TRPBF")
      (footprint "easyedapro:TO-252-3_L6.5-W5.8-P4.58-BL")
      (fields (field (name "Manufacturer") "Infineon(英飞凌)"))
      (libsource (lib "easyedapro") (part "IRLR2905TRPBF"))
    )
    (comp (ref "R50")
      (value "1kΩ")
      (footprint "easyedapro:R0402")
      (fields
        (field (name "Manufacturer Part") "0402WGF1001TCE")
        (field (name "Manufacturer") "UNI-ROYAL(厚声)")
      )
      (libsource (lib "easyedapro") (part "0402WGF1001TCE"))
    )
    (comp (ref "R51")
      (value "1kΩ")
      (footprint "easyedapro:R0402")
      (fields
        (field (name "Manufacturer Part") "0402WGF1001TCE")
        (field (name "Manufacturer") "UNI-ROYAL(厚声)")
      )
      (libsource (lib "easyedapro") (part "0402WGF1001TCE"))
    )
    (comp (ref "R52")
      (value "33Ω")
      (footprint "easyedapro:R0402")
      (fields
        (field (name "Manufacturer Part") "0402WGF330JTCE")
        (field (name "Manufacturer") "UNI-ROYAL(厚声)")
      )
      (libsource (lib "easyedapro") (part "0402WGF330JTCE"))
    )
    (comp (ref "R54")
      (value "1.5kΩ")
      (footprint "easyedapro:R0402")
      (fields
        (field (name "Manufacturer Part") "0402WGF1501TCE")
        (field (name "Manufacturer") "UNI-ROYAL(厚声)")
      )
      (libsource (lib "easyedapro") (part "0402WGF1501TCE"))
    )
    (comp (ref "R55")
      (value "33Ω")
      (footprint "easyedapro:R0402")
      (fields
        (field (name "Manufacturer Part") "0402WGF330JTCE")
        (field (name "Manufacturer") "UNI-ROYAL(厚声)")
      )
      (libsource (lib "easyedapro") (part "0402WGF330JTCE"))
    )
    (comp (ref "R56")
      (value "12.1kΩ")
      (footprint "easyedapro:R0402")
      (fields
        (field (name "Manufacturer Part") "0402WGF1212TCE")
        (field (name "Manufacturer") "UNI-ROYAL(厚声)")
      )
      (libsource (lib "easyedapro") (part "0402WGF1212TCE"))
    )
    (comp (ref "R57")
      (value "49.9Ω")
      (footprint "easyedapro:R0402")
      (fields
        (field (name "Manufacturer Part") "0402WGF499JTCE")
        (field (name "Manufacturer") "UNI-ROYAL(厚声)")
      )
      (libsource (lib "easyedapro") (part "0402WGF499JTCE"))
    )
    (comp (ref "R58")
      (value "49.9Ω")
      (footprint "easyedapro:R0402")
      (fields
        (field (name "Manufacturer Part") "0402WGF499JTCE")
        (field (name "Manufacturer") "UNI-ROYAL(厚声)")
      )
      (libsource (lib "easyedapro") (part "0402WGF499JTCE"))
    )
    (comp (ref "R59")
      (value "49.9Ω")
      (footprint "easyedapro:R0402")
      (fields
        (field (name "Manufacturer Part") "0402WGF499JTCE")
        (field (name "Manufacturer") "UNI-ROYAL(厚声)")
      )
      (libsource (lib "easyedapro") (part "0402WGF499JTCE"))
    )
    (comp (ref "R60")
      (value "49.9Ω")
      (footprint "easyedapro:R0402")
      (fields
        (field (name "Manufacturer Part") "0402WGF499JTCE")
        (field (name "Manufacturer") "UNI-ROYAL(厚声)")
      )
      (libsource (lib "easyedapro") (part "0402WGF499JTCE"))
    )
    (comp (ref "R64")
      (value "1kΩ")
      (footprint "easyedapro:R0402")
      (fields
        (field (name "Manufacturer Part") "0402WGF1001TCE")
        (field (name "Manufacturer") "UNI-ROYAL(厚声)")
      )
      (libsource (lib "easyedapro") (part "0402WGF1001TCE"))
    )
    (comp (ref "R65")
      (value "1kΩ")
      (footprint "easyedapro:R0402")
      (fields
        (field (name "Manufacturer Part") "0402WGF1001TCE")
        (field (name "Manufacturer") "UNI-ROYAL(厚声)")
      )
      (libsource (lib "easyedapro") (part "0402WGF1001TCE"))
    )
    (comp (ref "R67")
      (value "1kΩ")
      (footprint "easyedapro:R0402")
      (fields
        (field (name "Manufacturer Part") "0402WGF1001TCE")
        (field (name "Manufacturer") "UNI-ROYAL(厚声)")
      )
      (libsource (lib "easyedapro") (part "0402WGF1001TCE"))
    )
    (comp (ref "R68")
      (value "10kΩ")
      (footprint "easyedapro:R0603")
      (fields
        (field (name "Manufacturer Part") "0603WAF1002T5E")
        (field (name "Manufacturer") "UNI-ROYAL(厚声)")
      )
      (libsource (lib "easyedapro") (part "0603WAF1002T5E"))
    )
    (comp (ref "R69")
      (value "10kΩ")
      (footprint "easyedapro:R0603")
      (fields
        (field (name "Manufacturer Part") "0603WAF1002T5E")
        (field (name "Manufacturer") "UNI-ROYAL(厚声)")
      )
      (libsource (lib "easyedapro") (part "0603WAF1002T5E"))
    )
    (comp (ref "R70")
      (value "10kΩ")
      (footprint "easyedapro:R0603")
      (fields
        (field (name "Manufacturer Part") "0603WAF1002T5E")
        (field (name "Manufacturer") "UNI-ROYAL(厚声)")
      )
      (libsource (lib "easyedapro") (part "0603WAF1002T5E"))
    )
    (comp (ref "R71")
      (value "10kΩ")
      (footprint "easyedapro:R0603")
      (fields
        (field (name "Manufacturer Part") "0603WAF1002T5E")
        (field (name "Manufacturer") "UNI-ROYAL(厚声)")
      )
      (libsource (lib "easyedapro") (part "0603WAF1002T5E"))
    )
    (comp (ref "R73")
      (value "10kΩ")
      (footprint "easyedapro:R0603")
      (fields
        (field (name "Manufacturer Part") "0603WAF1002T5E")
        (field (name "Manufacturer") "UNI-ROYAL(厚声)")
      )
      (libsource (lib "easyedapro") (part "0603WAF1002T5E"))
    )
    (comp (ref "R74")
      (value "47kΩ")
      (footprint "easyedapro:R0805")
      (fields
        (field (name "Manufacturer Part") "0805W8F4702T5E")
        (field (name "Manufacturer") "UNI-ROYAL(厚声)")
      )
      (libsource (lib "easyedapro") (part "0805W8F4702T5E"))
    )
    (comp (ref "RESET")
      (value "~")
      (footprint "easyedapro:SOLDERJUMPER_REFLOW_NOPASTE")
      (libsource (lib "easyedapro") (part "Solder Jumper"))
    )
    (comp (ref "U8")
      (value "ESP32-WROOM-32E-N4")
      (footprint "easyedapro:WIFI-SMD_ESP32-WROOM-32E")
      (fields (field (name "Manufacturer") "ESPRESSIF(乐鑫)"))
      (libsource (lib "easyedapro") (part "ESP32-WROOM-32E(4MB)"))
    )
    (comp (ref "U10")
      (value "AMS1117-3.3")
      (footprint "easyedapro:SOT-223-3_L6.5-W3.4-P2.30-LS7.0-BR")
      (fields (field (name "Manufacturer") "AMS"))
      (libsource (lib "easyedapro") (part "AMS1117-3.3"))
    )
    (comp (ref "U11")
      (value "LAN8720A-CP-TR")
      (footprint "easyedapro:QFN-24_L4.0-W4.0-P0.50-BL-EP2.6")
      (fields (field (name "Manufacturer") "MICROCHIP(美国微芯)"))
      (libsource (lib "easyedapro") (part "LAN8720A-CP-TR"))
    )
  )
  (nets
    (net (code "1") (name "+5V") (class "Default")
      (node (ref "C20") (pin "1") (pinfunction "1_1") (pintype "input"))
      (node (ref "C21") (pin "1") (pinfunction "1_1") (pintype "input"))
      (node (ref "C32") (pin "2") (pinfunction "2_2") (pintype "input"))
      (node (ref "C39") (pin "2") (pinfunction "2_2") (pintype "input"))
      (node (ref "ICSP") (pin "3") (pinfunction "3_3") (pintype "input"))
      (node (ref "L2") (pin "2") (pinfunction "2_2") (pintype "input"))
      (node (ref "R49") (pin "2") (pinfunction "2_2") (pintype "input"))
      (node (ref "U10") (pin "3") (pinfunction "VIN_3") (pintype "unspecified"))
    )
    (net (code "2") (name "+24V") (class "Default")
      (node (ref "C28") (pin "1") (pinfunction "1_1") (pintype "input"))
      (node (ref "C29") (pin "1") (pinfunction "1_1") (pintype "input"))
      (node (ref "L3") (pin "2") (pinfunction "2_2") (pintype "input"))
      (node (ref "P1") (pin "2") (pinfunction "2_2") (pintype "input"))
      (node (ref "R48") (pin "2") (pinfunction "2_2") (pintype "unspecified"))
    )
    (net (code "3") (name "3V3") (class "Default")
      (node (ref "C33") (pin "2") (pinfunction "2_2") (pintype "input"))
      (node (ref "C35") (pin "1") (pinfunction "1_1") (pintype "input"))
      (node (ref "C36") (pin "1") (pinfunction "1_1") (pintype "unspecified"))
      (node (ref "C38") (pin "2") (pinfunction "2_2") (pintype "input"))
      (node (ref "C41") (pin "2") (pinfunction "2_2") (pintype "input"))
      (node (ref "C42") (pin "2") (pinfunction "2_2") (pintype "unspecified"))
      (node (ref "L4") (pin "2") (pinfunction "2_2") (pintype "input"))
      (node (ref "LED1") (pin "2") (pinfunction "A_2") (pintype "input"))
      (node (ref "LED2") (pin "2") (pinfunction "A_2") (pintype "unspecified"))
      (node (ref "OSC1") (pin "4") (pinfunction "VDD_4") (pintype "input"))
      (node (ref "R54") (pin "1") (pinfunction "1_1") (pintype "input"))
      (node (ref "R69") (pin "2") (pinfunction "2_2") (pintype "input"))
      (node (ref "R70") (pin "2") (pinfunction "2_2") (pintype "input"))
      (node (ref "R71") (pin "2") (pinfunction "2_2") (pintype "input"))
      (node (ref "R73") (pin "1") (pinfunction "1_1") (pintype "input"))
      (node (ref "U10") (pin "2") (pinfunction "VOUT_2") (pintype "unspecified"))
      (node (ref "U10") (pin "4") (pinfunction "VOUT_4") (pintype "unspecified"))
      (node (ref "U11") (pin "9") (pinfunction "VDDIO_9") (pintype "input"))
      (node (ref "U8") (pin "2") (pinfunction "3V3_2") (pintype "unspecified"))
    )
    (net (code "4") (name "AVDD") (class "Default")
      (node (ref "C43") (pin "1") (pinfunction "1_1") (pintype "input"))
      (node (ref "C44") (pin "1") (pinfunction "1_1") (pintype "unspecified"))
      (node (ref "L4") (pin "1") (pinfunction "1_1") (pintype "input"))
      (node (ref "PoE-IN") (pin "L2") (pinfunction "LED1+_L2") (pintype "unspecified"))
      (node (ref "PoE-IN") (pin "L3") (pinfunction "LED2-/+_L3") (pintype "unspecified"))
      (node (ref "R57") (pin "2") (pinfunction "2_2") (pintype "input"))
      (node (ref "R58") (pin "2") (pinfunction "2_2") (pintype "input"))
      (node (ref "R59") (pin "2") (pinfunction "2_2") (pintype "input"))
      (node (ref "R60") (pin "2") (pinfunction "2_2") (pintype "input"))
      (node (ref "U11") (pin "1") (pinfunction "VDD2A_1") (pintype "input"))
      (node (ref "U11") (pin "19") (pinfunction "VDD1A_19") (pintype "input"))
    )
    (net (code "5") (name "CLK50M") (class "Default")
      (node (ref "OSC1") (pin "3") (pinfunction "OUT_3") (pintype "input"))
      (node (ref "R52") (pin "1") (pinfunction "1_1") (pintype "input"))
      (node (ref "R55") (pin "2") (pinfunction "2_2") (pintype "input"))
    )
    (net (code "6") (name "EN") (class "Default")
      (node (ref "C47") (pin "2") (pinfunction "2_2") (pintype "input"))
      (node (ref "R73") (pin "2") (pinfunction "2_2") (pintype "input"))
      (node (ref "RESET") (pin "1") (pinfunction "1_1") (pintype "input"))
      (node (ref "U8") (pin "3") (pinfunction "EN_3") (pintype "unspecified"))
    )
    (net (code "7") (name "ETH2X_LED1") (class "Default")
      (node (ref "PoE-IN") (pin "L1") (pinfunction "LED1-_L1") (pintype "unspecified"))
      (node (ref "R51") (pin "1") (pinfunction "1_1") (pintype "input"))
    )
    (net (code "8") (name "ETH2X_LED2") (class "Default")
      (node (ref "PoE-IN") (pin "L4") (pinfunction "LED2+/-_L4") (pintype "unspecified"))
      (node (ref "R50") (pin "1") (pinfunction "1_1") (pintype "input"))
    )
    (net (code "9") (name "ETH2X_RX+") (class "Default")
      (node (ref "PoE-IN") (pin "R4") (pinfunction "TD2+_R4") (pintype "unspecified"))
      (node (ref "R57") (pin "1") (pinfunction "1_1") (pintype "input"))
      (node (ref "U11") (pin "23") (pinfunction "RXP_23") (pintype "input"))
    )
    (net (code "10") (name "ETH2X_RX-") (class "Default")
      (node (ref "PoE-IN") (pin "R5") (pinfunction "TD2-_R5") (pintype "unspecified"))
      (node (ref "R58") (pin "1") (pinfunction "1_1") (pintype "input"))
      (node (ref "U11") (pin "22") (pinfunction "RXN_22") (pintype "input"))
    )
    (net (code "11") (name "ETH2X_TX+") (class "Default")
      (node (ref "PoE-IN") (pin "R11") (pinfunction "TD1+_R11") (pintype "unspecified"))
      (node (ref "R59") (pin "1") (pinfunction "1_1") (pintype "input"))
      (node (ref "U11") (pin "21") (pinfunction "TXP_21") (pintype "input"))
    )
    (net (code "12") (name "ETH2X_TX-") (class "Default")
      (node (ref "PoE-IN") (pin "R10") (pinfunction "TD1-_R10") (pintype "unspecified"))
      (node (ref "R60") (pin "1") (pinfunction "1_1") (pintype "input"))
      (node (ref "U11") (pin "20") (pinfunction "TXN_20") (pintype "input"))
    )
    (net (code "13") (name "FB5V") (class "Default")
      (node (ref "R49") (pin "1") (pinfunction "1_1") (pintype "input"))
      (node (ref "Trim5V") (pin "3") (pinfunction "3_3") (pintype "unspecified"))
      (node (ref "U6") (pin "6") (pinfunction "FB_6") (pintype "input"))
    )
    (net (code "14") (name "FB24V") (class "Default")
      (node (ref "R48") (pin "1") (pinfunction "1_1") (pintype "unspecified"))
      (node (ref "Trim24v") (pin "3") (pinfunction "3_3") (pintype "unspecified"))
      (node (ref "U7") (pin "6") (pinfunction "FB_6") (pintype "input"))
    )
    (net (code "15") (name "GND") (class "Default")
      (node (ref "C1") (pin "1") (pinfunction "1_1") (pintype "input"))
      (node (ref "D3") (pin "2") (pinfunction "A_2") (pintype "input"))
      (node (ref "D6") (pin "2") (pinfunction "-_2") (pintype "input"))
      (node (ref "D7") (pin "2") (pinfunction "-_2") (pintype "input"))
      (node (ref "R4") (pin "1") (pinfunction "1_1") (pintype "unspecified"))
      (node (ref "R6") (pin "1") (pinfunction "1_1") (pintype "unspecified"))
      (node (ref "U1") (pin "4") (pinfunction "VSS_4") (pintype "input"))
    )
    (net (code "16") (name "IO0_RMII_EMAC_REF_CLK") (class "Default")
      (node (ref "PROG-EN") (pin "1") (pinfunction "1_1") (pintype "input"))
      (node (ref "R55") (pin "1") (pinfunction "1_1") (pintype "input"))
      (node (ref "R69") (pin "1") (pinfunction "1_1") (pintype "input"))
      (node (ref "U11") (pin "14") (pinfunction "nINT/REFCLKO_14") (pintype "input"))
      (node (ref "U8") (pin "25") (pinfunction "IO0_25") (pintype "unspecified"))
    )
    (net (code "17") (name "IO1_TXD0") (class "Default")
      (node (ref "ICSP") (pin "5") (pinfunction "5_5") (pintype "input"))
      (node (ref "U8") (pin "35") (pinfunction "TXD0_35") (pintype "unspecified"))
    )
    (net (code "18") (name "IO3_RXD0") (class "Default")
      (node (ref "ICSP") (pin "4") (pinfunction "4_4") (pintype "input"))
      (node (ref "U8") (pin "34") (pinfunction "RXD0_34") (pintype "unspecified"))
    )
    (net (code "19") (name "IO13_RMII_EMAC_RX_ER") (class "Default")
      (node (ref "R70") (pin "1") (pinfunction "1_1") (pintype "input"))
      (node (ref "U11") (pin "10") (pinfunction "RXER/PHYAD0_10") (pintype "input"))
      (node (ref "U8") (pin "16") (pinfunction "IO13_16") (pintype "unspecified"))
    )
    (net (code "20") (name "IO16_OSC_EN") (class "Default")
      (node (ref "OSC1") (pin "1") (pinfunction "Tri-state_1") (pintype "input"))
      (node (ref "R68") (pin "2") (pinfunction "2_2") (pintype "input"))
      (node (ref "U8") (pin "27") (pinfunction "IO16_27") (pintype "unspecified"))
    )
    (net (code "21") (name "IO17_COLD") (class "Default")
      (node (ref "R65") (pin "2") (pinfunction "2_2") (pintype "input"))
      (node (ref "U8") (pin "28") (pinfunction "IO17_28") (pintype "unspecified"))
    )
    (net (code "22") (name "IO18_RMII_MDIO") (class "Default")
      (node (ref "R54") (pin "2") (pinfunction "2_2") (pintype "input"))
      (node (ref "U11") (pin "12") (pinfunction "MDIO_12") (pintype "input"))
      (node (ref "U8") (pin "30") (pinfunction "IO18_30") (pintype "unspecified"))
    )
    (net (code "23") (name "IO19_RMII_EMAC_TXD0") (class "Default")
      (node (ref "U11") (pin "17") (pinfunction "TXD0_17") (pintype "input"))
      (node (ref "U8") (pin "31") (pinfunction "IO19_31") (pintype "unspecified"))
    )
    (net (code "24") (name "IO21_RMII_EMAC_TX_EN") (class "Default")
      (node (ref "U11") (pin "16") (pinfunction "TXEN_16") (pintype "input"))
      (node (ref "U8") (pin "33") (pinfunction "IO21_33") (pintype "unspecified"))
    )
    (net (code "25") (name "IO22_RMII_EMAC_TXD1") (class "Default")
      (node (ref "U11") (pin "18") (pinfunction "TXD1_18") (pintype "input"))
      (node (ref "U8") (pin "36") (pinfunction "IO22_36") (pintype "unspecified"))
    )
    (net (code "26") (name "IO23_RMII_MDC") (class "Default")
      (node (ref "U11") (pin "13") (pinfunction "MDC_13") (pintype "input"))
      (node (ref "U8") (pin "37") (pinfunction "IO23_37") (pintype "unspecified"))
    )
    (net (code "27") (name "IO25_RMII_EMAC_RXD0") (class "Default")
      (node (ref "U11") (pin "8") (pinfunction "RXD0/MODE0_8") (pintype "input"))
      (node (ref "U8") (pin "10") (pinfunction "IO25_10") (pintype "unspecified"))
    )
    (net (code "28") (name "IO26_RMII_EMAC_RXD1") (class "Default")
      (node (ref "U11") (pin "7") (pinfunction "RXD1/MODE1_7") (pintype "input"))
      (node (ref "U8") (pin "11") (pinfunction "IO26_11") (pintype "unspecified"))
    )
    (net (code "29") (name "IO27_RMII_EMAC_CRS_DV") (class "Default")
      (node (ref "U11") (pin "11") (pinfunction "CRS_DV/MODE2_11") (pintype "input"))
      (node (ref "U8") (pin "12") (pinfunction "IO27_12") (pintype "unspecified"))
    )
    (net (code "30") (name "IO32_CFG") (class "Default")
      (node (ref "R67") (pin "1") (pinfunction "1_1") (pintype "input"))
      (node (ref "U8") (pin "8") (pinfunction "IO32_8") (pintype "unspecified"))
    )
    (net (code "31") (name "IO33_HOT") (class "Default")
      (node (ref "R64") (pin "2") (pinfunction "2_2") (pintype "input"))
      (node (ref "U8") (pin "9") (pinfunction "IO33_9") (pintype "unspecified"))
    )
    (net (code "32") (name "NRST") (class "Default")
      (node (ref "C40") (pin "2") (pinfunction "2_2") (pintype "input"))
      (node (ref "R71") (pin "1") (pinfunction "1_1") (pintype "input"))
      (node (ref "U11") (pin "15") (pinfunction "nRST_15") (pintype "input"))
    )
    (net (code "33") (name "Net-(C22-Pad2)") (class "Default")
      (node (ref "C22") (pin "2") (pinfunction "2_2") (pintype "input"))
      (node (ref "R29") (pin "1") (pinfunction "1_1") (pintype "input"))
    )
    (net (code "34") (name "Net-(C30-Pad2)") (class "Default")
      (node (ref "C30") (pin "2") (pinfunction "2_2") (pintype "input"))
      (node (ref "R40") (pin "1") (pinfunction "1_1") (pintype "input"))
    )
    (net (code "35") (name "Net-(D5-C)") (class "Default")
      (node (ref "D5") (pin "1") (pinfunction "C_1") (pintype "input"))
      (node (ref "Q3") (pin "1") (pinfunction "G_1") (pintype "unspecified"))
      (node (ref "R7") (pin "1") (pinfunction "1_1") (pintype "input"))
      (node (ref "U1") (pin "6") (pinfunction "PG_6") (pintype "input"))
    )
    (net (code "36") (name "Net-(Dummy-Pad1)") (class "Default")
      (node (ref "Dummy") (pin "1") (pinfunction "1_1") (pintype "input"))
      (node (ref "Rdummy") (pin "2") (pinfunction "2_2") (pintype "unspecified"))
    )
    (net (code "37") (name "Net-(LED1-K)") (class "Default")
      (node (ref "LED1") (pin "1") (pinfunction "K_1") (pintype "input"))
      (node (ref "R64") (pin "1") (pinfunction "1_1") (pintype "input"))
    )
    (net (code "38") (name "Net-(LED2-K)") (class "Default")
      (node (ref "LED2") (pin "1") (pinfunction "K_1") (pintype "unspecified"))
      (node (ref "R65") (pin "1") (pinfunction "1_1") (pintype "input"))
    )
    (net (code "39") (name "Net-(PWROK-A)") (class "Default")
      (node (ref "PWROK") (pin "1") (pinfunction "A_1") (pintype "unspecified"))
      (node (ref "R13") (pin "1") (pinfunction "1_1") (pintype "input"))
    )
    (net (code "40") (name "Net-(PWROK-K)") (class "Default")
      (node (ref "PWROK") (pin "2") (pinfunction "K_2") (pintype "unspecified"))
      (node (ref "Q3") (pin "3") (pinfunction "D_3") (pintype "unspecified"))
    )
    (net (code "41") (name "Net-(PoE-IN-TCT1)") (class "Default")
      (node (ref "PoE-IN") (pin "R12") (pinfunction "TCT1_R12") (pintype "unspecified"))
      (node (ref "PoE-IN") (pin "R6") (pinfunction "TCT2_R6") (pintype "unspecified"))
    )
    (net (code "42") (name "Net-(PoE-IN-TCT3)") (class "Default")
      (node (ref "PoE-IN") (pin "R1") (pinfunction "TCT3_R1") (pintype "unspecified"))
      (node (ref "PoE-IN") (pin "R7") (pinfunction "TCT4_R7") (pintype "unspecified"))
    )
    (net (code "43") (name "Net-(PoE-IN-VC1)") (class "Default")
      (node (ref "D7") (pin "3") (pinfunction "AC_3") (pintype "input"))
      (node (ref "PoE-IN") (pin "R13") (pinfunction "VC1_R13") (pintype "unspecified"))
    )
    (net (code "44") (name "Net-(PoE-IN-VC2)") (class "Default")
      (node (ref "D7") (pin "4") (pinfunction "AC_4") (pintype "input"))
      (node (ref "PoE-IN") (pin "R14") (pinfunction "VC2_R14") (pintype "unspecified"))
    )
    (net (code "45") (name "Net-(PoE-IN-VC3)") (class "Default")
      (node (ref "D6") (pin "4") (pinfunction "AC_4") (pintype "input"))
      (node (ref "PoE-IN") (pin "R15") (pinfunction "VC3_R15") (pintype "unspecified"))
    )
    (net (code "46") (name "Net-(PoE-IN-VC4)") (class "Default")
      (node (ref "D6") (pin "3") (pinfunction "AC_3") (pintype "input"))
      (node (ref "PoE-IN") (pin "R16") (pinfunction "VC4_R16") (pintype "unspecified"))
    )
    (net (code "47") (name "Net-(Q1-D)") (class "Default")
      (node (ref "P1") (pin "1") (pinfunction "1_1") (pintype "input"))
      (node (ref "Q1") (pin "2") (pinfunction "D_2") (pintype "unspecified"))
    )
    (net (code "48") (name "Net-(Q1-G)") (class "Default")
      (node (ref "Q1") (pin "1") (pinfunction "G_1") (pintype "unspecified"))
      (node (ref "R67") (pin "2") (pinfunction "2_2") (pintype "input"))
      (node (ref "R74") (pin "2") (pinfunction "2_2") (pintype "input"))
    )
    (net (code "49") (name "Net-(R35-Pad2)") (class "Default")
      (node (ref "R35") (pin "2") (pinfunction "2_2") (pintype "input"))
      (node (ref "Trim5V") (pin "1") (pinfunction "1_1") (pintype "unspecified"))
      (node (ref "Trim5V") (pin "2") (pinfunction "2_2") (pintype "unspecified"))
    )
    (net (code "50") (name "Net-(R46-Pad2)") (class "Default")
      (node (ref "R46") (pin "2") (pinfunction "2_2") (pintype "input"))
      (node (ref "Trim24v") (pin "1") (pinfunction "1_1") (pintype "unspecified"))
      (node (ref "Trim24v") (pin "2") (pinfunction "2_2") (pintype "unspecified"))
    )
    (net (code "51") (name "Net-(U1-CLASS)") (class "Default")
      (node (ref "R4") (pin "2") (pinfunction "2_2") (pintype "unspecified"))
      (node (ref "U1") (pin "2") (pinfunction "CLASS_2") (pintype "input"))
    )
    (net (code "52") (name "Net-(U1-DET)") (class "Default")
      (node (ref "R5") (pin "1") (pinfunction "1_1") (pintype "input"))
      (node (ref "U1") (pin "3") (pinfunction "DET_3") (pintype "input"))
    )
    (net (code "53") (name "Net-(U1-ILIM)") (class "Default")
      (node (ref "R6") (pin "2") (pinfunction "2_2") (pintype "unspecified"))
      (node (ref "U1") (pin "1") (pinfunction "ILIM_1") (pintype "input"))
    )
    (net (code "54") (name "Net-(U6-BOOT)") (class "Default")
      (node (ref "C19") (pin "2") (pinfunction "2_2") (pintype "input"))
      (node (ref "U6") (pin "1") (pinfunction "BOOT_1") (pintype "input"))
    )
    (net (code "55") (name "Net-(U6-COMP)") (class "Default")
      (node (ref "C23") (pin "2") (pinfunction "2_2") (pintype "input"))
      (node (ref "R29") (pin "2") (pinfunction "2_2") (pintype "input"))
      (node (ref "U6") (pin "7") (pinfunction "COMP_7") (pintype "input"))
    )
    (net (code "56") (name "Net-(U6-EN)") (class "Default")
      (node (ref "R26") (pin "2") (pinfunction "2_2") (pintype "unspecified"))
      (node (ref "R36") (pin "1") (pinfunction "1_1") (pintype "input"))
      (node (ref "U6") (pin "3") (pinfunction "EN_3") (pintype "input"))
    )
    (net (code "57") (name "Net-(U6-RT{slash}CLK)") (class "Default")
      (node (ref "R27") (pin "2") (pinfunction "2_2") (pintype "input"))
      (node (ref "U6") (pin "5") (pinfunction "RT/CLK_5") (pintype "input"))
    )
    (net (code "58") (name "Net-(U6-SS{slash}TR)") (class "Default")
      (node (ref "C18") (pin "2") (pinfunction "2_2") (pintype "input"))
      (node (ref "U6") (pin "4") (pinfunction "SS/TR_4") (pintype "input"))
    )
    (net (code "59") (name "Net-(U6-SW)") (class "Default")
      (node (ref "C19") (pin "1") (pinfunction "1_1") (pintype "input"))
      (node (ref "D8") (pin "3") (pinfunction "3_3") (pintype "input"))
      (node (ref "L2") (pin "1") (pinfunction "1_1") (pintype "input"))
      (node (ref "U6") (pin "9") (pinfunction "SW_9") (pintype "input"))
    )
    (net (code "60") (name "Net-(U7-BOOT)") (class "Default")
      (node (ref "C27") (pin "2") (pinfunction "2_2") (pintype "input"))
      (node (ref "U7") (pin "1") (pinfunction "BOOT_1") (pintype "input"))
    )
    (net (code "61") (name "Net-(U7-COMP)") (class "Default")
      (node (ref "C31") (pin "2") (pinfunction "2_2") (pintype "input"))
      (node (ref "R40") (pin "2") (pinfunction "2_2") (pintype "input"))
      (node (ref "U7") (pin "7") (pinfunction "COMP_7") (pintype "input"))
    )
    (net (code "62") (name "Net-(U7-EN)") (class "Default")
      (node (ref "R37") (pin "2") (pinfunction "2_2") (pintype "unspecified"))
      (node (ref "R47") (pin "1") (pinfunction "1_1") (pintype "input"))
      (node (ref "U7") (pin "3") (pinfunction "EN_3") (pintype "input"))
    )
    (net (code "63") (name "Net-(U7-RT{slash}CLK)") (class "Default")
      (node (ref "R38") (pin "2") (pinfunction "2_2") (pintype "input"))
      (node (ref "U7") (pin "5") (pinfunction "RT/CLK_5") (pintype "input"))
    )
    (net (code "64") (name "Net-(U7-SS{slash}TR)") (class "Default")
      (node (ref "C26") (pin "2") (pinfunction "2_2") (pintype "input"))
      (node (ref "U7") (pin "4") (pinfunction "SS/TR_4") (pintype "input"))
    )
    (net (code "65") (name "Net-(U7-SW)") (class "Default")
      (node (ref "C27") (pin "1") (pinfunction "1_1") (pintype "input"))
      (node (ref "D9") (pin "3") (pinfunction "3_3") (pintype "input"))
      (node (ref "L3") (pin "1") (pinfunction "1_1") (pintype "input"))
      (node (ref "U7") (pin "9") (pinfunction "SW_9") (pintype "input"))
    )
    (net (code "66") (name "Net-(U11-LED1{slash}REGOFF)") (class "Default")
      (node (ref "R51") (pin "2") (pinfunction "2_2") (pintype "input"))
      (node (ref "U11") (pin "3") (pinfunction "LED1/REGOFF_3") (pintype "input"))
    )
    (net (code "67") (name "Net-(U11-LED2{slash}nINTSEL)") (class "Default")
      (node (ref "R50") (pin "2") (pinfunction "2_2") (pintype "input"))
      (node (ref "U11") (pin "2") (pinfunction "LED2/nINTSEL_2") (pintype "input"))
    )
    (net (code "68") (name "Net-(U11-RBIAS)") (class "Default")
      (node (ref "R56") (pin "1") (pinfunction "1_1") (pintype "input"))
      (node (ref "U11") (pin "24") (pinfunction "RBIAS_24") (pintype "input"))
    )
    (net (code "69") (name "OSCIN") (class "Default")
      (node (ref "R52") (pin "2") (pinfunction "2_2") (pintype "input"))
      (node (ref "U11") (pin "5") (pinfunction "XTAL1/CLKIN_5") (pintype "input"))
    )
    (net (code "70") (name "PSUGND") (class "Default")
      (node (ref "C16") (pin "1") (pinfunction "1_1") (pintype "input"))
      (node (ref "C17") (pin "1") (pinfunction "1_1") (pintype "input"))
      (node (ref "C18") (pin "1") (pinfunction "1_1") (pintype "input"))
      (node (ref "C2") (pin "2") (pinfunction "2_2") (pintype "input"))
      (node (ref "C20") (pin "2") (pinfunction "2_2") (pintype "input"))
      (node (ref "C21") (pin "2") (pinfunction "2_2") (pintype "input"))
      (node (ref "C22") (pin "1") (pinfunction "1_1") (pintype "input"))
      (node (ref "C23") (pin "1") (pinfunction "1_1") (pintype "input"))
      (node (ref "C24") (pin "1") (pinfunction "1_1") (pintype "input"))
      (node (ref "C25") (pin "1") (pinfunction "1_1") (pintype "input"))
      (node (ref "C26") (pin "1") (pinfunction "1_1") (pintype "input"))
      (node (ref "C28") (pin "2") (pinfunction "2_2") (pintype "input"))
      (node (ref "C29") (pin "2") (pinfunction "2_2") (pintype "input"))
      (node (ref "C30") (pin "1") (pinfunction "1_1") (pintype "input"))
      (node (ref "C31") (pin "1") (pinfunction "1_1") (pintype "input"))
      (node (ref "C32") (pin "1") (pinfunction "1_1") (pintype "input"))
      (node (ref "C33") (pin "1") (pinfunction "1_1") (pintype "input"))
      (node (ref "C35") (pin "2") (pinfunction "2_2") (pintype "input"))
      (node (ref "C36") (pin "2") (pinfunction "2_2") (pintype "unspecified"))
      (node (ref "C38") (pin "1") (pinfunction "1_1") (pintype "input"))
      (node (ref "C39") (pin "1") (pinfunction "1_1") (pintype "input"))
      (node (ref "C40") (pin "1") (pinfunction "1_1") (pintype "input"))
      (node (ref "C41") (pin "1") (pinfunction "1_1") (pintype "input"))
      (node (ref "C42") (pin "1") (pinfunction "1_1") (pintype "unspecified"))
      (node (ref "C43") (pin "2") (pinfunction "2_2") (pintype "input"))
      (node (ref "C44") (pin "2") (pinfunction "2_2") (pintype "unspecified"))
      (node (ref "C45") (pin "1") (pinfunction "1_1") (pintype "input"))
      (node (ref "C46") (pin "1") (pinfunction "1_1") (pintype "input"))
      (node (ref "C47") (pin "1") (pinfunction "1_1") (pintype "input"))
      (node (ref "D5") (pin "2") (pinfunction "A_2") (pintype "input"))
      (node (ref "D8") (pin "1") (pinfunction "1_1") (pintype "input"))
      (node (ref "D8") (pin "2") (pinfunction "2_2") (pintype "input"))
      (node (ref "D9") (pin "1") (pinfunction "1_1") (pintype "input"))
      (node (ref "D9") (pin "2") (pinfunction "2_2") (pintype "input"))
      (node (ref "ICSP") (pin "1") (pinfunction "1_1") (pintype "input"))
      (node (ref "OSC1") (pin "2") (pinfunction "GND_2") (pintype "input"))
      (node (ref "PROG-EN") (pin "2") (pinfunction "2_2") (pintype "input"))
      (node (ref "PoE-IN") (pin "0") (pinfunction "0_0") (pintype "unspecified"))
      (node (ref "Q1") (pin "3") (pinfunction "S_3") (pintype "unspecified"))
      (node (ref "Q3") (pin "2") (pinfunction "S_2") (pintype "unspecified"))
      (node (ref "R26") (pin "1") (pinfunction "1_1") (pintype "unspecified"))
      (node (ref "R27") (pin "1") (pinfunction "1_1") (pintype "input"))
      (node (ref "R35") (pin "1") (pinfunction "1_1") (pintype "input"))
      (node (ref "R37") (pin "1") (pinfunction "1_1") (pintype "unspecified"))
      (node (ref "R38") (pin "1") (pinfunction "1_1") (pintype "input"))
      (node (ref "R46") (pin "1") (pinfunction "1_1") (pintype "input"))
      (node (ref "R56") (pin "2") (pinfunction "2_2") (pintype "input"))
      (node (ref "R68") (pin "1") (pinfunction "1_1") (pintype "input"))
      (node (ref "R74") (pin "1") (pinfunction "1_1") (pintype "input"))
      (node (ref "RESET") (pin "2") (pinfunction "2_2") (pintype "input"))
      (node (ref "Rdummy") (pin "1") (pinfunction "1_1") (pintype "unspecified"))
      (node (ref "U1") (pin "5") (pinfunction "RTN_5") (pintype "input"))
      (node (ref "U10") (pin "1") (pinfunction "GND_1") (pintype "unspecified"))
      (node (ref "U11") (pin "25") (pinfunction "EP_25") (pintype "input"))
      (node (ref "U6") (pin "11") (pinfunction "EP_11") (pintype "input"))
      (node (ref "U6") (pin "8") (pinfunction "GND_8") (pintype "input"))
      (node (ref "U7") (pin "11") (pinfunction "EP_11") (pintype "input"))
      (node (ref "U7") (pin "8") (pinfunction "GND_8") (pintype "input"))
      (node (ref "U8") (pin "1") (pinfunction "GND_1") (pintype "unspecified"))
      (node (ref "U8") (pin "15") (pinfunction "GND_15") (pintype "unspecified"))
      (node (ref "U8") (pin "38") (pinfunction "GND_38") (pintype "unspecified"))
      (node (ref "U8") (pin "39") (pinfunction "GND_39") (pintype "unspecified"))
    )
    (net (code "71") (name "VCC") (class "Default")
      (node (ref "C1") (pin "2") (pinfunction "2_2") (pintype "input"))
      (node (ref "C16") (pin "2") (pinfunction "2_2") (pintype "input"))
      (node (ref "C17") (pin "2") (pinfunction "2_2") (pintype "input"))
      (node (ref "C2") (pin "1") (pinfunction "1_1") (pintype "input"))
      (node (ref "C24") (pin "2") (pinfunction "2_2") (pintype "input"))
      (node (ref "C25") (pin "2") (pinfunction "2_2") (pintype "input"))
      (node (ref "D3") (pin "1") (pinfunction "K_1") (pintype "input"))
      (node (ref "D6") (pin "1") (pinfunction "+_1") (pintype "input"))
      (node (ref "D7") (pin "1") (pinfunction "+_1") (pintype "input"))
      (node (ref "Dummy") (pin "2") (pinfunction "2_2") (pintype "input"))
      (node (ref "R13") (pin "2") (pinfunction "2_2") (pintype "input"))
      (node (ref "R36") (pin "2") (pinfunction "2_2") (pintype "input"))
      (node (ref "R47") (pin "2") (pinfunction "2_2") (pintype "input"))
      (node (ref "R5") (pin "2") (pinfunction "2_2") (pintype "input"))
      (node (ref "R7") (pin "2") (pinfunction "2_2") (pintype "input"))
      (node (ref "U1") (pin "8") (pinfunction "VDD_8") (pintype "input"))
      (node (ref "U6") (pin "2") (pinfunction "VIN_2") (pintype "input"))
      (node (ref "U7") (pin "2") (pinfunction "VIN_2") (pintype "input"))
    )
    (net (code "72") (name "VDDCR") (class "Default")
      (node (ref "C45") (pin "2") (pinfunction "2_2") (pintype "input"))
      (node (ref "C46") (pin "2") (pinfunction "2_2") (pintype "input"))
      (node (ref "U11") (pin "6") (pinfunction "VDDCR_6") (pintype "input"))
    )
    (net (code "73") (name "unconnected-(H1-Pad1)") (class "Default")
      (node (ref "H1") (pin "1") (pinfunction "1_1") (pintype "input+no_connect"))
    )
    (net (code "74") (name "unconnected-(ICSP-Pad2)") (class "Default")
      (node (ref "ICSP") (pin "2") (pinfunction "2_2") (pintype "input+no_connect"))
    )
    (net (code "75") (name "unconnected-(ICSP-Pad6)") (class "Default")
      (node (ref "ICSP") (pin "6") (pinfunction "6_6") (pintype "input+no_connect"))
    )
    (net (code "76") (name "unconnected-(PoE-IN-TD3+-PadR3)") (class "Default")
      (node (ref "PoE-IN") (pin "R3") (pinfunction "TD3+_R3") (pintype "unspecified+no_connect"))
    )
    (net (code "77") (name "unconnected-(PoE-IN-TD3--PadR2)") (class "Default")
      (node (ref "PoE-IN") (pin "R2") (pinfunction "TD3-_R2") (pintype "unspecified+no_connect"))
    )
    (net (code "78") (name "unconnected-(PoE-IN-TD4+-PadR8)") (class "Default")
      (node (ref "PoE-IN") (pin "R8") (pinfunction "TD4+_R8") (pintype "unspecified+no_connect"))
    )
    (net (code "79") (name "unconnected-(PoE-IN-TD4--PadR9)") (class "Default")
      (node (ref "PoE-IN") (pin "R9") (pinfunction "TD4-_R9") (pintype "unspecified+no_connect"))
    )
    (net (code "80") (name "unconnected-(U1-NC-Pad7)") (class "Default")
      (node (ref "U1") (pin "7") (pinfunction "NC_7") (pintype "input+no_connect"))
    )
    (net (code "81") (name "unconnected-(U6-PWRGD-Pad10)") (class "Default")
      (node (ref "U6") (pin "10") (pinfunction "PWRGD_10") (pintype "input+no_connect"))
    )
    (net (code "82") (name "unconnected-(U7-PWRGD-Pad10)") (class "Default")
      (node (ref "U7") (pin "10") (pinfunction "PWRGD_10") (pintype "input+no_connect"))
    )
    (net (code "83") (name "unconnected-(U8-IO2-Pad24)") (class "Default")
      (node (ref "U8") (pin "24") (pinfunction "IO2_24") (pintype "unspecified+no_connect"))
    )
    (net (code "84") (name "unconnected-(U8-IO4-Pad26)") (class "Default")
      (node (ref "U8") (pin "26") (pinfunction "IO4_26") (pintype "unspecified+no_connect"))
    )
    (net (code "85") (name "unconnected-(U8-IO5-Pad29)") (class "Default")
      (node (ref "U8") (pin "29") (pinfunction "IO5_29") (pintype "unspecified+no_connect"))
    )
    (net (code "86") (name "unconnected-(U8-IO12-Pad14)") (class "Default")
      (node (ref "U8") (pin "14") (pinfunction "IO12_14") (pintype "unspecified+no_connect"))
    )
    (net (code "87") (name "unconnected-(U8-IO14-Pad13)") (class "Default")
      (node (ref "U8") (pin "13") (pinfunction "IO14_13") (pintype "unspecified+no_connect"))
    )
    (net (code "88") (name "unconnected-(U8-IO15-Pad23)") (class "Default")
      (node (ref "U8") (pin "23") (pinfunction "IO15_23") (pintype "unspecified+no_connect"))
    )
    (net (code "89") (name "unconnected-(U8-IO34-Pad6)") (class "Default")
      (node (ref "U8") (pin "6") (pinfunction "IO34_6") (pintype "unspecified+no_connect"))
    )
    (net (code "90") (name "unconnected-(U8-IO35-Pad7)") (class "Default")
      (node (ref "U8") (pin "7") (pinfunction "IO35_7") (pintype "unspecified+no_connect"))
    )
    (net (code "91") (name "unconnected-(U8-NC-Pad17)") (class "Default")
      (node (ref "U8") (pin "17") (pinfunction "NC_17") (pintype "unspecified+no_connect"))
    )
    (net (code "92") (name "unconnected-(U8-NC-Pad18)") (class "Default")
      (node (ref "U8") (pin "18") (pinfunction "NC_18") (pintype "unspecified+no_connect"))
    )
    (net (code "93") (name "unconnected-(U8-NC-Pad19)") (class "Default")
      (node (ref "U8") (pin "19") (pinfunction "NC_19") (pintype "unspecified+no_connect"))
    )
    (net (code "94") (name "unconnected-(U8-NC-Pad20)") (class "Default")
      (node (ref "U8") (pin "20") (pinfunction "NC_20") (pintype "unspecified+no_connect"))
    )
    (net (code "95") (name "unconnected-(U8-NC-Pad21)") (class "Default")
      (node (ref "U8") (pin "21") (pinfunction "NC_21") (pintype "unspecified+no_connect"))
    )
    (net (code "96") (name "unconnected-(U8-NC-Pad22)") (class "Default")
      (node (ref "U8") (pin "22") (pinfunction "NC_22") (pintype "unspecified+no_connect"))
    )
    (net (code "97") (name "unconnected-(U8-NC-Pad32)") (class "Default")
      (node (ref "U8") (pin "32") (pinfunction "NC_32") (pintype "unspecified+no_connect"))
    )
    (net (code "98") (name "unconnected-(U8-SENSOR_VN-Pad5)") (class "Default")
      (node (ref "U8") (pin "5") (pinfunction "SENSOR_VN_5") (pintype "unspecified+no_connect"))
    )
    (net (code "99") (name "unconnected-(U8-SENSOR_VP-Pad4)") (class "Default")
      (node (ref "U8") (pin "4") (pinfunction "SENSOR_VP_4") (pintype "unspecified+no_connect"))
    )
    (net (code "100") (name "unconnected-(U11-XTAL2-Pad4)") (class "Default")
      (node (ref "U11") (pin "4") (pinfunction "XTAL2_4") (pintype "input+no_connect"))
    )
  )
)
